# Mosfets.net
KiCad netlist of a schematic drawn in Altium Designer
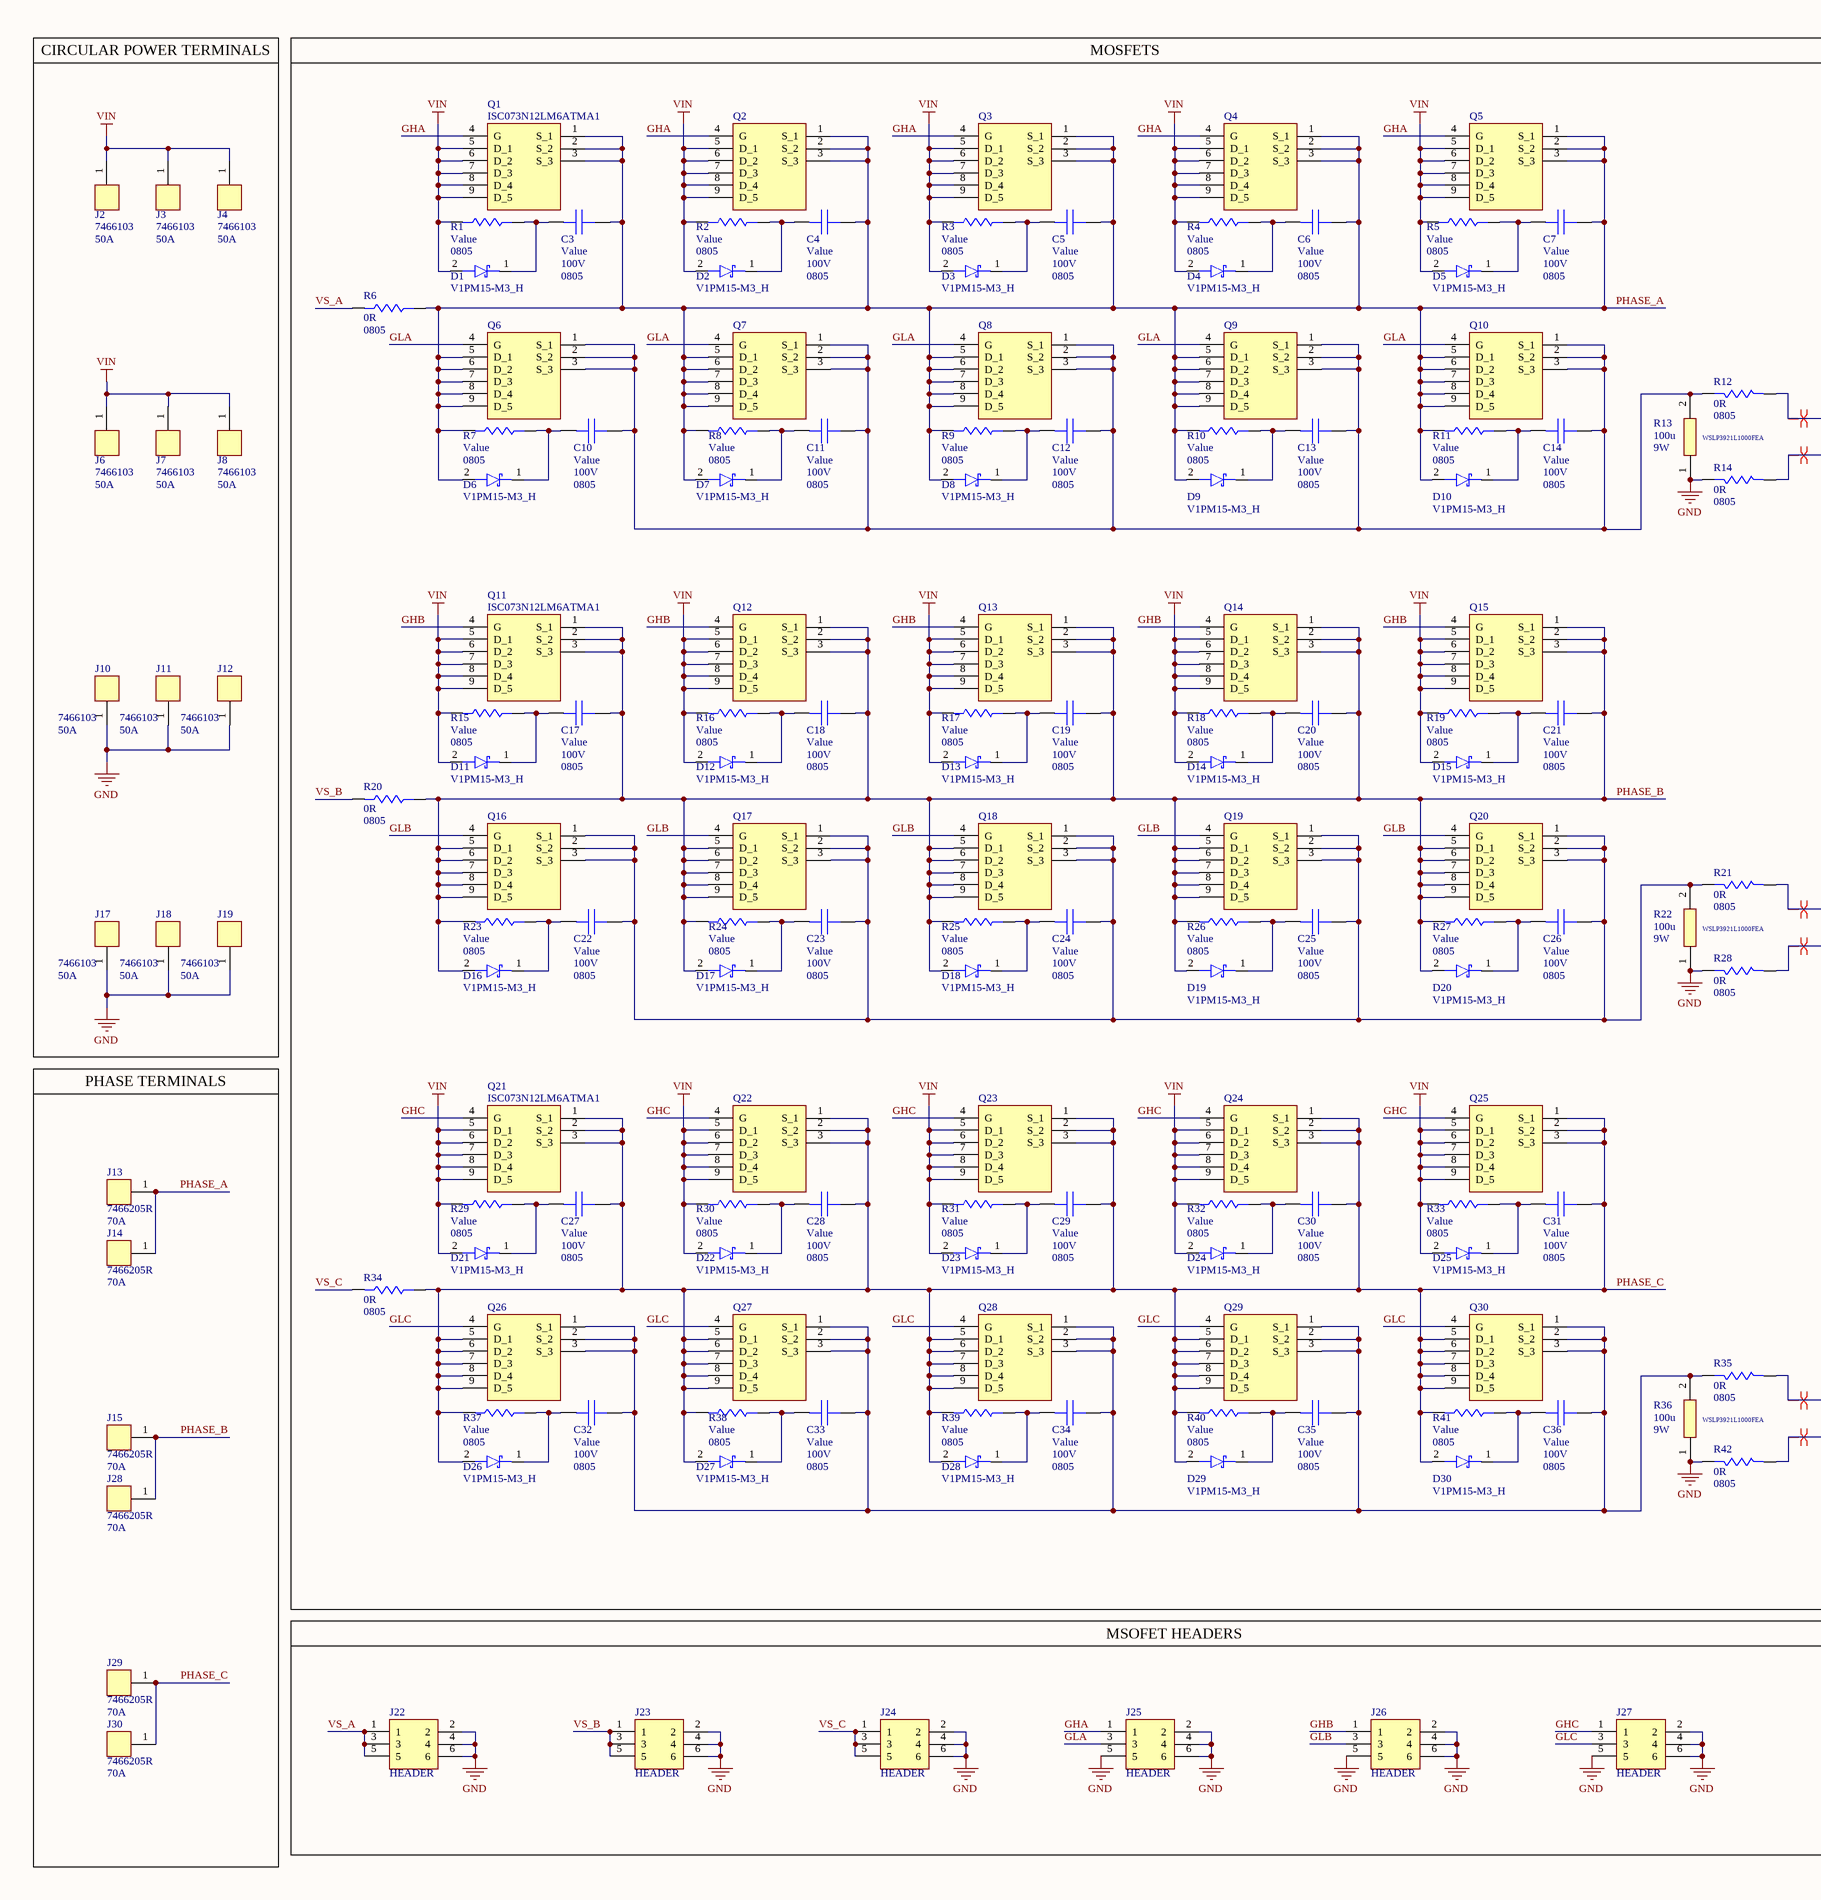
[diagram p0: Mosfets.SchDoc, left]
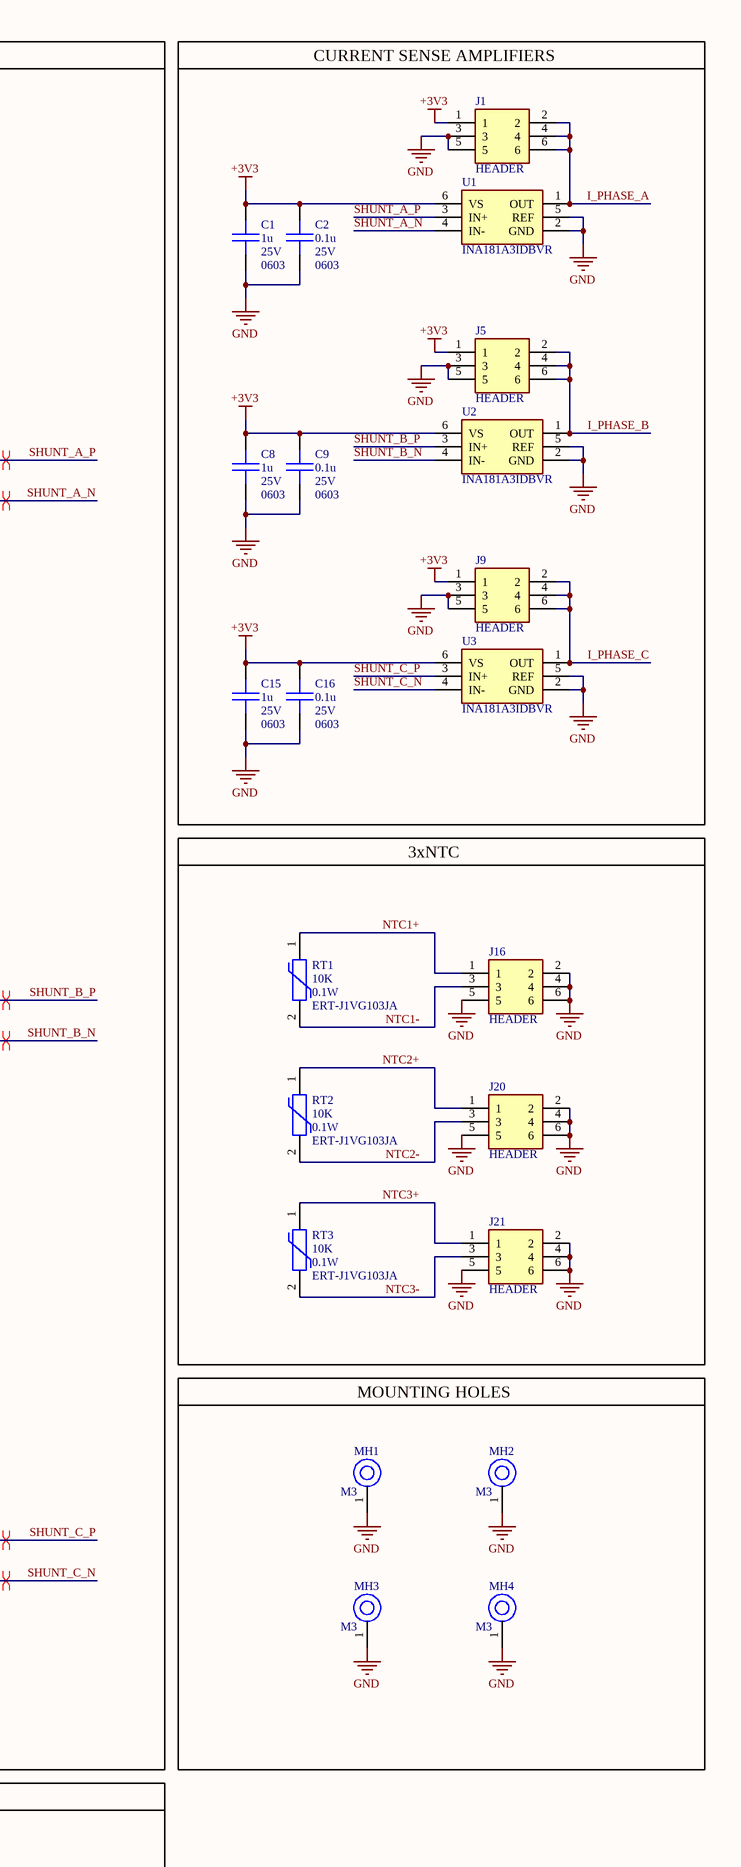
[diagram p1: Mosfets.SchDoc, right]

(export (version "E")
  (design (tool "Eeschema 10.0.6"))
  (components
    (comp (ref "C1")
      (value "0603")
      (footprint "C_0603")
      (description "SMD Chip Capacitor - 0603")
      (fields (field (name "VOLTAGE") "25V") (field (name "ALTIUM_VALUE") "1u"))
      (libsource (lib "My_Integrated_Lib") (part "CAP_0603"))
    )
    (comp (ref "C2")
      (value "0603")
      (footprint "C_0603")
      (description "SMD Chip Capacitor - 0603")
      (fields (field (name "VOLTAGE") "25V") (field (name "ALTIUM_VALUE") "0.1u"))
      (libsource (lib "My_Integrated_Lib") (part "CAP_0603"))
    )
    (comp (ref "C3")
      (value "0805")
      (footprint "C_0805")
      (description "SMD Chip Capacitor - 0805")
      (fields (field (name "VOLTAGE") "100V") (field (name "ALTIUM_VALUE") "Value"))
      (libsource (lib "My_Integrated_Lib") (part "CAP_0805"))
    )
    (comp (ref "C4")
      (value "0805")
      (footprint "C_0805")
      (description "SMD Chip Capacitor - 0805")
      (fields (field (name "VOLTAGE") "100V") (field (name "ALTIUM_VALUE") "Value"))
      (libsource (lib "My_Integrated_Lib") (part "CAP_0805"))
    )
    (comp (ref "C5")
      (value "0805")
      (footprint "C_0805")
      (description "SMD Chip Capacitor - 0805")
      (fields (field (name "VOLTAGE") "100V") (field (name "ALTIUM_VALUE") "Value"))
      (libsource (lib "My_Integrated_Lib") (part "CAP_0805"))
    )
    (comp (ref "C6")
      (value "0805")
      (footprint "C_0805")
      (description "SMD Chip Capacitor - 0805")
      (fields (field (name "VOLTAGE") "100V") (field (name "ALTIUM_VALUE") "Value"))
      (libsource (lib "My_Integrated_Lib") (part "CAP_0805"))
    )
    (comp (ref "C7")
      (value "0805")
      (footprint "C_0805")
      (description "SMD Chip Capacitor - 0805")
      (fields (field (name "VOLTAGE") "100V") (field (name "ALTIUM_VALUE") "Value"))
      (libsource (lib "My_Integrated_Lib") (part "CAP_0805"))
    )
    (comp (ref "C8")
      (value "0603")
      (footprint "C_0603")
      (description "SMD Chip Capacitor - 0603")
      (fields (field (name "VOLTAGE") "25V") (field (name "ALTIUM_VALUE") "1u"))
      (libsource (lib "My_Integrated_Lib") (part "CAP_0603"))
    )
    (comp (ref "C9")
      (value "0603")
      (footprint "C_0603")
      (description "SMD Chip Capacitor - 0603")
      (fields (field (name "VOLTAGE") "25V") (field (name "ALTIUM_VALUE") "0.1u"))
      (libsource (lib "My_Integrated_Lib") (part "CAP_0603"))
    )
    (comp (ref "C10")
      (value "0805")
      (footprint "C_0805")
      (description "SMD Chip Capacitor - 0805")
      (fields (field (name "VOLTAGE") "100V") (field (name "ALTIUM_VALUE") "Value"))
      (libsource (lib "My_Integrated_Lib") (part "CAP_0805"))
    )
    (comp (ref "C11")
      (value "0805")
      (footprint "C_0805")
      (description "SMD Chip Capacitor - 0805")
      (fields (field (name "VOLTAGE") "100V") (field (name "ALTIUM_VALUE") "Value"))
      (libsource (lib "My_Integrated_Lib") (part "CAP_0805"))
    )
    (comp (ref "C12")
      (value "0805")
      (footprint "C_0805")
      (description "SMD Chip Capacitor - 0805")
      (fields (field (name "VOLTAGE") "100V") (field (name "ALTIUM_VALUE") "Value"))
      (libsource (lib "My_Integrated_Lib") (part "CAP_0805"))
    )
    (comp (ref "C13")
      (value "0805")
      (footprint "C_0805")
      (description "SMD Chip Capacitor - 0805")
      (fields (field (name "VOLTAGE") "100V") (field (name "ALTIUM_VALUE") "Value"))
      (libsource (lib "My_Integrated_Lib") (part "CAP_0805"))
    )
    (comp (ref "C14")
      (value "0805")
      (footprint "C_0805")
      (description "SMD Chip Capacitor - 0805")
      (fields (field (name "VOLTAGE") "100V") (field (name "ALTIUM_VALUE") "Value"))
      (libsource (lib "My_Integrated_Lib") (part "CAP_0805"))
    )
    (comp (ref "C15")
      (value "0603")
      (footprint "C_0603")
      (description "SMD Chip Capacitor - 0603")
      (fields (field (name "VOLTAGE") "25V") (field (name "ALTIUM_VALUE") "1u"))
      (libsource (lib "My_Integrated_Lib") (part "CAP_0603"))
    )
    (comp (ref "C16")
      (value "0603")
      (footprint "C_0603")
      (description "SMD Chip Capacitor - 0603")
      (fields (field (name "VOLTAGE") "25V") (field (name "ALTIUM_VALUE") "0.1u"))
      (libsource (lib "My_Integrated_Lib") (part "CAP_0603"))
    )
    (comp (ref "C17")
      (value "0805")
      (footprint "C_0805")
      (description "SMD Chip Capacitor - 0805")
      (fields (field (name "VOLTAGE") "100V") (field (name "ALTIUM_VALUE") "Value"))
      (libsource (lib "My_Integrated_Lib") (part "CAP_0805"))
    )
    (comp (ref "C18")
      (value "0805")
      (footprint "C_0805")
      (description "SMD Chip Capacitor - 0805")
      (fields (field (name "VOLTAGE") "100V") (field (name "ALTIUM_VALUE") "Value"))
      (libsource (lib "My_Integrated_Lib") (part "CAP_0805"))
    )
    (comp (ref "C19")
      (value "0805")
      (footprint "C_0805")
      (description "SMD Chip Capacitor - 0805")
      (fields (field (name "VOLTAGE") "100V") (field (name "ALTIUM_VALUE") "Value"))
      (libsource (lib "My_Integrated_Lib") (part "CAP_0805"))
    )
    (comp (ref "C20")
      (value "0805")
      (footprint "C_0805")
      (description "SMD Chip Capacitor - 0805")
      (fields (field (name "VOLTAGE") "100V") (field (name "ALTIUM_VALUE") "Value"))
      (libsource (lib "My_Integrated_Lib") (part "CAP_0805"))
    )
    (comp (ref "C21")
      (value "0805")
      (footprint "C_0805")
      (description "SMD Chip Capacitor - 0805")
      (fields (field (name "VOLTAGE") "100V") (field (name "ALTIUM_VALUE") "Value"))
      (libsource (lib "My_Integrated_Lib") (part "CAP_0805"))
    )
    (comp (ref "C22")
      (value "0805")
      (footprint "C_0805")
      (description "SMD Chip Capacitor - 0805")
      (fields (field (name "VOLTAGE") "100V") (field (name "ALTIUM_VALUE") "Value"))
      (libsource (lib "My_Integrated_Lib") (part "CAP_0805"))
    )
    (comp (ref "C23")
      (value "0805")
      (footprint "C_0805")
      (description "SMD Chip Capacitor - 0805")
      (fields (field (name "VOLTAGE") "100V") (field (name "ALTIUM_VALUE") "Value"))
      (libsource (lib "My_Integrated_Lib") (part "CAP_0805"))
    )
    (comp (ref "C24")
      (value "0805")
      (footprint "C_0805")
      (description "SMD Chip Capacitor - 0805")
      (fields (field (name "VOLTAGE") "100V") (field (name "ALTIUM_VALUE") "Value"))
      (libsource (lib "My_Integrated_Lib") (part "CAP_0805"))
    )
    (comp (ref "C25")
      (value "0805")
      (footprint "C_0805")
      (description "SMD Chip Capacitor - 0805")
      (fields (field (name "VOLTAGE") "100V") (field (name "ALTIUM_VALUE") "Value"))
      (libsource (lib "My_Integrated_Lib") (part "CAP_0805"))
    )
    (comp (ref "C26")
      (value "0805")
      (footprint "C_0805")
      (description "SMD Chip Capacitor - 0805")
      (fields (field (name "VOLTAGE") "100V") (field (name "ALTIUM_VALUE") "Value"))
      (libsource (lib "My_Integrated_Lib") (part "CAP_0805"))
    )
    (comp (ref "C27")
      (value "0805")
      (footprint "C_0805")
      (description "SMD Chip Capacitor - 0805")
      (fields (field (name "VOLTAGE") "100V") (field (name "ALTIUM_VALUE") "Value"))
      (libsource (lib "My_Integrated_Lib") (part "CAP_0805"))
    )
    (comp (ref "C28")
      (value "0805")
      (footprint "C_0805")
      (description "SMD Chip Capacitor - 0805")
      (fields (field (name "VOLTAGE") "100V") (field (name "ALTIUM_VALUE") "Value"))
      (libsource (lib "My_Integrated_Lib") (part "CAP_0805"))
    )
    (comp (ref "C29")
      (value "0805")
      (footprint "C_0805")
      (description "SMD Chip Capacitor - 0805")
      (fields (field (name "VOLTAGE") "100V") (field (name "ALTIUM_VALUE") "Value"))
      (libsource (lib "My_Integrated_Lib") (part "CAP_0805"))
    )
    (comp (ref "C30")
      (value "0805")
      (footprint "C_0805")
      (description "SMD Chip Capacitor - 0805")
      (fields (field (name "VOLTAGE") "100V") (field (name "ALTIUM_VALUE") "Value"))
      (libsource (lib "My_Integrated_Lib") (part "CAP_0805"))
    )
    (comp (ref "C31")
      (value "0805")
      (footprint "C_0805")
      (description "SMD Chip Capacitor - 0805")
      (fields (field (name "VOLTAGE") "100V") (field (name "ALTIUM_VALUE") "Value"))
      (libsource (lib "My_Integrated_Lib") (part "CAP_0805"))
    )
    (comp (ref "C32")
      (value "0805")
      (footprint "C_0805")
      (description "SMD Chip Capacitor - 0805")
      (fields (field (name "VOLTAGE") "100V") (field (name "ALTIUM_VALUE") "Value"))
      (libsource (lib "My_Integrated_Lib") (part "CAP_0805"))
    )
    (comp (ref "C33")
      (value "0805")
      (footprint "C_0805")
      (description "SMD Chip Capacitor - 0805")
      (fields (field (name "VOLTAGE") "100V") (field (name "ALTIUM_VALUE") "Value"))
      (libsource (lib "My_Integrated_Lib") (part "CAP_0805"))
    )
    (comp (ref "C34")
      (value "0805")
      (footprint "C_0805")
      (description "SMD Chip Capacitor - 0805")
      (fields (field (name "VOLTAGE") "100V") (field (name "ALTIUM_VALUE") "Value"))
      (libsource (lib "My_Integrated_Lib") (part "CAP_0805"))
    )
    (comp (ref "C35")
      (value "0805")
      (footprint "C_0805")
      (description "SMD Chip Capacitor - 0805")
      (fields (field (name "VOLTAGE") "100V") (field (name "ALTIUM_VALUE") "Value"))
      (libsource (lib "My_Integrated_Lib") (part "CAP_0805"))
    )
    (comp (ref "C36")
      (value "0805")
      (footprint "C_0805")
      (description "SMD Chip Capacitor - 0805")
      (fields (field (name "VOLTAGE") "100V") (field (name "ALTIUM_VALUE") "Value"))
      (libsource (lib "My_Integrated_Lib") (part "CAP_0805"))
    )
    (comp (ref "D1")
      (value "V1PM15-M3_H")
      (footprint "DO-219AD-2")
      (description "Schottky Diode, 150V, 1A, Vf: 1.13V")
      (libsource (lib "My_Integrated_Lib") (part "DIODE_SCHOTTKY_V1PM15-M3_H"))
    )
    (comp (ref "D2")
      (value "V1PM15-M3_H")
      (footprint "DO-219AD-2")
      (description "Schottky Diode, 150V, 1A, Vf: 1.13V")
      (libsource (lib "My_Integrated_Lib") (part "DIODE_SCHOTTKY_V1PM15-M3_H"))
    )
    (comp (ref "D3")
      (value "V1PM15-M3_H")
      (footprint "DO-219AD-2")
      (description "Schottky Diode, 150V, 1A, Vf: 1.13V")
      (libsource (lib "My_Integrated_Lib") (part "DIODE_SCHOTTKY_V1PM15-M3_H"))
    )
    (comp (ref "D4")
      (value "V1PM15-M3_H")
      (footprint "DO-219AD-2")
      (description "Schottky Diode, 150V, 1A, Vf: 1.13V")
      (libsource (lib "My_Integrated_Lib") (part "DIODE_SCHOTTKY_V1PM15-M3_H"))
    )
    (comp (ref "D5")
      (value "V1PM15-M3_H")
      (footprint "DO-219AD-2")
      (description "Schottky Diode, 150V, 1A, Vf: 1.13V")
      (libsource (lib "My_Integrated_Lib") (part "DIODE_SCHOTTKY_V1PM15-M3_H"))
    )
    (comp (ref "D6")
      (value "V1PM15-M3_H")
      (footprint "DO-219AD-2")
      (description "Schottky Diode, 150V, 1A, Vf: 1.13V")
      (libsource (lib "My_Integrated_Lib") (part "DIODE_SCHOTTKY_V1PM15-M3_H"))
    )
    (comp (ref "D7")
      (value "V1PM15-M3_H")
      (footprint "DO-219AD-2")
      (description "Schottky Diode, 150V, 1A, Vf: 1.13V")
      (libsource (lib "My_Integrated_Lib") (part "DIODE_SCHOTTKY_V1PM15-M3_H"))
    )
    (comp (ref "D8")
      (value "V1PM15-M3_H")
      (footprint "DO-219AD-2")
      (description "Schottky Diode, 150V, 1A, Vf: 1.13V")
      (libsource (lib "My_Integrated_Lib") (part "DIODE_SCHOTTKY_V1PM15-M3_H"))
    )
    (comp (ref "D9")
      (value "V1PM15-M3_H")
      (footprint "DO-219AD-2")
      (description "Schottky Diode, 150V, 1A, Vf: 1.13V")
      (libsource (lib "My_Integrated_Lib") (part "DIODE_SCHOTTKY_V1PM15-M3_H"))
    )
    (comp (ref "D10")
      (value "V1PM15-M3_H")
      (footprint "DO-219AD-2")
      (description "Schottky Diode, 150V, 1A, Vf: 1.13V")
      (libsource (lib "My_Integrated_Lib") (part "DIODE_SCHOTTKY_V1PM15-M3_H"))
    )
    (comp (ref "D11")
      (value "V1PM15-M3_H")
      (footprint "DO-219AD-2")
      (description "Schottky Diode, 150V, 1A, Vf: 1.13V")
      (libsource (lib "My_Integrated_Lib") (part "DIODE_SCHOTTKY_V1PM15-M3_H"))
    )
    (comp (ref "D12")
      (value "V1PM15-M3_H")
      (footprint "DO-219AD-2")
      (description "Schottky Diode, 150V, 1A, Vf: 1.13V")
      (libsource (lib "My_Integrated_Lib") (part "DIODE_SCHOTTKY_V1PM15-M3_H"))
    )
    (comp (ref "D13")
      (value "V1PM15-M3_H")
      (footprint "DO-219AD-2")
      (description "Schottky Diode, 150V, 1A, Vf: 1.13V")
      (libsource (lib "My_Integrated_Lib") (part "DIODE_SCHOTTKY_V1PM15-M3_H"))
    )
    (comp (ref "D14")
      (value "V1PM15-M3_H")
      (footprint "DO-219AD-2")
      (description "Schottky Diode, 150V, 1A, Vf: 1.13V")
      (libsource (lib "My_Integrated_Lib") (part "DIODE_SCHOTTKY_V1PM15-M3_H"))
    )
    (comp (ref "D15")
      (value "V1PM15-M3_H")
      (footprint "DO-219AD-2")
      (description "Schottky Diode, 150V, 1A, Vf: 1.13V")
      (libsource (lib "My_Integrated_Lib") (part "DIODE_SCHOTTKY_V1PM15-M3_H"))
    )
    (comp (ref "D16")
      (value "V1PM15-M3_H")
      (footprint "DO-219AD-2")
      (description "Schottky Diode, 150V, 1A, Vf: 1.13V")
      (libsource (lib "My_Integrated_Lib") (part "DIODE_SCHOTTKY_V1PM15-M3_H"))
    )
    (comp (ref "D17")
      (value "V1PM15-M3_H")
      (footprint "DO-219AD-2")
      (description "Schottky Diode, 150V, 1A, Vf: 1.13V")
      (libsource (lib "My_Integrated_Lib") (part "DIODE_SCHOTTKY_V1PM15-M3_H"))
    )
    (comp (ref "D18")
      (value "V1PM15-M3_H")
      (footprint "DO-219AD-2")
      (description "Schottky Diode, 150V, 1A, Vf: 1.13V")
      (libsource (lib "My_Integrated_Lib") (part "DIODE_SCHOTTKY_V1PM15-M3_H"))
    )
    (comp (ref "D19")
      (value "V1PM15-M3_H")
      (footprint "DO-219AD-2")
      (description "Schottky Diode, 150V, 1A, Vf: 1.13V")
      (libsource (lib "My_Integrated_Lib") (part "DIODE_SCHOTTKY_V1PM15-M3_H"))
    )
    (comp (ref "D20")
      (value "V1PM15-M3_H")
      (footprint "DO-219AD-2")
      (description "Schottky Diode, 150V, 1A, Vf: 1.13V")
      (libsource (lib "My_Integrated_Lib") (part "DIODE_SCHOTTKY_V1PM15-M3_H"))
    )
    (comp (ref "D21")
      (value "V1PM15-M3_H")
      (footprint "DO-219AD-2")
      (description "Schottky Diode, 150V, 1A, Vf: 1.13V")
      (libsource (lib "My_Integrated_Lib") (part "DIODE_SCHOTTKY_V1PM15-M3_H"))
    )
    (comp (ref "D22")
      (value "V1PM15-M3_H")
      (footprint "DO-219AD-2")
      (description "Schottky Diode, 150V, 1A, Vf: 1.13V")
      (libsource (lib "My_Integrated_Lib") (part "DIODE_SCHOTTKY_V1PM15-M3_H"))
    )
    (comp (ref "D23")
      (value "V1PM15-M3_H")
      (footprint "DO-219AD-2")
      (description "Schottky Diode, 150V, 1A, Vf: 1.13V")
      (libsource (lib "My_Integrated_Lib") (part "DIODE_SCHOTTKY_V1PM15-M3_H"))
    )
    (comp (ref "D24")
      (value "V1PM15-M3_H")
      (footprint "DO-219AD-2")
      (description "Schottky Diode, 150V, 1A, Vf: 1.13V")
      (libsource (lib "My_Integrated_Lib") (part "DIODE_SCHOTTKY_V1PM15-M3_H"))
    )
    (comp (ref "D25")
      (value "V1PM15-M3_H")
      (footprint "DO-219AD-2")
      (description "Schottky Diode, 150V, 1A, Vf: 1.13V")
      (libsource (lib "My_Integrated_Lib") (part "DIODE_SCHOTTKY_V1PM15-M3_H"))
    )
    (comp (ref "D26")
      (value "V1PM15-M3_H")
      (footprint "DO-219AD-2")
      (description "Schottky Diode, 150V, 1A, Vf: 1.13V")
      (libsource (lib "My_Integrated_Lib") (part "DIODE_SCHOTTKY_V1PM15-M3_H"))
    )
    (comp (ref "D27")
      (value "V1PM15-M3_H")
      (footprint "DO-219AD-2")
      (description "Schottky Diode, 150V, 1A, Vf: 1.13V")
      (libsource (lib "My_Integrated_Lib") (part "DIODE_SCHOTTKY_V1PM15-M3_H"))
    )
    (comp (ref "D28")
      (value "V1PM15-M3_H")
      (footprint "DO-219AD-2")
      (description "Schottky Diode, 150V, 1A, Vf: 1.13V")
      (libsource (lib "My_Integrated_Lib") (part "DIODE_SCHOTTKY_V1PM15-M3_H"))
    )
    (comp (ref "D29")
      (value "V1PM15-M3_H")
      (footprint "DO-219AD-2")
      (description "Schottky Diode, 150V, 1A, Vf: 1.13V")
      (libsource (lib "My_Integrated_Lib") (part "DIODE_SCHOTTKY_V1PM15-M3_H"))
    )
    (comp (ref "D30")
      (value "V1PM15-M3_H")
      (footprint "DO-219AD-2")
      (description "Schottky Diode, 150V, 1A, Vf: 1.13V")
      (libsource (lib "My_Integrated_Lib") (part "DIODE_SCHOTTKY_V1PM15-M3_H"))
    )
    (comp (ref "J1")
      (value "HEADER")
      (footprint "HEADER_MALE_2X3_1.27MM")
      (libsource (lib "My_Integrated_Lib") (part "HEADER_SMD_2X3_1.27MM"))
    )
    (comp (ref "J2")
      (value "7466103")
      (footprint "7466203")
      (description "Terminals, SMT, M3 Thread, 50A")
      (fields (field (name "CURRENT") "50A"))
      (libsource (lib "My_Integrated_Lib") (part "TERMINAL_7466203"))
    )
    (comp (ref "J3")
      (value "7466103")
      (footprint "7466203")
      (description "Terminals, SMT, M3 Thread, 50A")
      (fields (field (name "CURRENT") "50A"))
      (libsource (lib "My_Integrated_Lib") (part "TERMINAL_7466203"))
    )
    (comp (ref "J4")
      (value "7466103")
      (footprint "7466203")
      (description "Terminals, SMT, M3 Thread, 50A")
      (fields (field (name "CURRENT") "50A"))
      (libsource (lib "My_Integrated_Lib") (part "TERMINAL_7466203"))
    )
    (comp (ref "J5")
      (value "HEADER")
      (footprint "HEADER_MALE_2X3_1.27MM")
      (libsource (lib "My_Integrated_Lib") (part "HEADER_SMD_2X3_1.27MM"))
    )
    (comp (ref "J6")
      (value "7466103")
      (footprint "7466203")
      (description "Terminals, SMT, M3 Thread, 50A")
      (fields (field (name "CURRENT") "50A"))
      (libsource (lib "My_Integrated_Lib") (part "TERMINAL_7466203"))
    )
    (comp (ref "J7")
      (value "7466103")
      (footprint "7466203")
      (description "Terminals, SMT, M3 Thread, 50A")
      (fields (field (name "CURRENT") "50A"))
      (libsource (lib "My_Integrated_Lib") (part "TERMINAL_7466203"))
    )
    (comp (ref "J8")
      (value "7466103")
      (footprint "7466203")
      (description "Terminals, SMT, M3 Thread, 50A")
      (fields (field (name "CURRENT") "50A"))
      (libsource (lib "My_Integrated_Lib") (part "TERMINAL_7466203"))
    )
    (comp (ref "J9")
      (value "HEADER")
      (footprint "HEADER_MALE_2X3_1.27MM")
      (libsource (lib "My_Integrated_Lib") (part "HEADER_SMD_2X3_1.27MM"))
    )
    (comp (ref "J10")
      (value "7466103")
      (footprint "7466203")
      (description "Terminals, SMT, M3 Thread, 50A")
      (fields (field (name "CURRENT") "50A"))
      (libsource (lib "") (part "TERMINAL_7466203_1"))
    )
    (comp (ref "J11")
      (value "7466103")
      (footprint "7466203")
      (description "Terminals, SMT, M3 Thread, 50A")
      (fields (field (name "CURRENT") "50A"))
      (libsource (lib "") (part "TERMINAL_7466203_1"))
    )
    (comp (ref "J12")
      (value "7466103")
      (footprint "7466203")
      (description "Terminals, SMT, M3 Thread, 50A")
      (fields (field (name "CURRENT") "50A"))
      (libsource (lib "") (part "TERMINAL_7466203_1"))
    )
    (comp (ref "J13")
      (value "7466205R")
      (footprint "7466205R")
      (description "Terminals, SMT, M5 Thread, 70A")
      (fields (field (name "CURRENT") "70A"))
      (libsource (lib "My_Integrated_Lib") (part "TERMINAL_7466205R"))
    )
    (comp (ref "J14")
      (value "7466205R")
      (footprint "7466205R")
      (description "Terminals, SMT, M5 Thread, 70A")
      (fields (field (name "CURRENT") "70A"))
      (libsource (lib "My_Integrated_Lib") (part "TERMINAL_7466205R"))
    )
    (comp (ref "J15")
      (value "7466205R")
      (footprint "7466205R")
      (description "Terminals, SMT, M5 Thread, 70A")
      (fields (field (name "CURRENT") "70A"))
      (libsource (lib "My_Integrated_Lib") (part "TERMINAL_7466205R"))
    )
    (comp (ref "J16")
      (value "HEADER")
      (footprint "HEADER_MALE_2X3_1.27MM")
      (libsource (lib "My_Integrated_Lib") (part "HEADER_SMD_2X3_1.27MM"))
    )
    (comp (ref "J17")
      (value "7466103")
      (footprint "7466203")
      (description "Terminals, SMT, M3 Thread, 50A")
      (fields (field (name "CURRENT") "50A"))
      (libsource (lib "") (part "TERMINAL_7466203_1"))
    )
    (comp (ref "J18")
      (value "7466103")
      (footprint "7466203")
      (description "Terminals, SMT, M3 Thread, 50A")
      (fields (field (name "CURRENT") "50A"))
      (libsource (lib "") (part "TERMINAL_7466203_1"))
    )
    (comp (ref "J19")
      (value "7466103")
      (footprint "7466203")
      (description "Terminals, SMT, M3 Thread, 50A")
      (fields (field (name "CURRENT") "50A"))
      (libsource (lib "") (part "TERMINAL_7466203_1"))
    )
    (comp (ref "J20")
      (value "HEADER")
      (footprint "HEADER_MALE_2X3_1.27MM")
      (libsource (lib "My_Integrated_Lib") (part "HEADER_SMD_2X3_1.27MM"))
    )
    (comp (ref "J21")
      (value "HEADER")
      (footprint "HEADER_MALE_2X3_1.27MM")
      (libsource (lib "My_Integrated_Lib") (part "HEADER_SMD_2X3_1.27MM"))
    )
    (comp (ref "J22")
      (value "HEADER")
      (footprint "HEADER_MALE_2X3_1.27MM")
      (libsource (lib "My_Integrated_Lib") (part "HEADER_SMD_2X3_1.27MM"))
    )
    (comp (ref "J23")
      (value "HEADER")
      (footprint "HEADER_MALE_2X3_1.27MM")
      (libsource (lib "My_Integrated_Lib") (part "HEADER_SMD_2X3_1.27MM"))
    )
    (comp (ref "J24")
      (value "HEADER")
      (footprint "HEADER_MALE_2X3_1.27MM")
      (libsource (lib "My_Integrated_Lib") (part "HEADER_SMD_2X3_1.27MM"))
    )
    (comp (ref "J25")
      (value "HEADER")
      (footprint "HEADER_MALE_2X3_1.27MM")
      (libsource (lib "My_Integrated_Lib") (part "HEADER_SMD_2X3_1.27MM"))
    )
    (comp (ref "J26")
      (value "HEADER")
      (footprint "HEADER_MALE_2X3_1.27MM")
      (libsource (lib "My_Integrated_Lib") (part "HEADER_SMD_2X3_1.27MM"))
    )
    (comp (ref "J27")
      (value "HEADER")
      (footprint "HEADER_MALE_2X3_1.27MM")
      (libsource (lib "My_Integrated_Lib") (part "HEADER_SMD_2X3_1.27MM"))
    )
    (comp (ref "J28")
      (value "7466205R")
      (footprint "7466205R")
      (description "Terminals, SMT, M5 Thread, 70A")
      (fields (field (name "CURRENT") "70A"))
      (libsource (lib "My_Integrated_Lib") (part "TERMINAL_7466205R"))
    )
    (comp (ref "J29")
      (value "7466205R")
      (footprint "7466205R")
      (description "Terminals, SMT, M5 Thread, 70A")
      (fields (field (name "CURRENT") "70A"))
      (libsource (lib "My_Integrated_Lib") (part "TERMINAL_7466205R"))
    )
    (comp (ref "J30")
      (value "7466205R")
      (footprint "7466205R")
      (description "Terminals, SMT, M5 Thread, 70A")
      (fields (field (name "CURRENT") "70A"))
      (libsource (lib "My_Integrated_Lib") (part "TERMINAL_7466205R"))
    )
    (comp (ref "MH1")
      (value "M3")
      (footprint "MOUNTING_HOLE_M3")
      (description "M3 Mounting Hole")
      (libsource (lib "My_Integrated_Lib") (part "Mounting_Hole_M3"))
    )
    (comp (ref "MH2")
      (value "M3")
      (footprint "MOUNTING_HOLE_M3")
      (description "M3 Mounting Hole")
      (libsource (lib "My_Integrated_Lib") (part "Mounting_Hole_M3"))
    )
    (comp (ref "MH3")
      (value "M3")
      (footprint "MOUNTING_HOLE_M3")
      (description "M3 Mounting Hole")
      (libsource (lib "My_Integrated_Lib") (part "Mounting_Hole_M3"))
    )
    (comp (ref "MH4")
      (value "M3")
      (footprint "MOUNTING_HOLE_M3")
      (description "M3 Mounting Hole")
      (libsource (lib "My_Integrated_Lib") (part "Mounting_Hole_M3"))
    )
    (comp (ref "Q1")
      (value "ISC073N12LM6ATMA1")
      (footprint "TDSON-8")
      (description "N Channel MOSFET, 120V, 86A, 7.3mR")
      (libsource (lib "My_Integrated_Lib") (part "MOSFET_N_ISC073N12LM6ATMA1"))
    )
    (comp (ref "Q2")
      (value "ISC073N12LM6ATMA1")
      (footprint "TDSON-8")
      (description "N Channel MOSFET, 120V, 86A, 7.3mR")
      (libsource (lib "My_Integrated_Lib") (part "MOSFET_N_ISC073N12LM6ATMA1"))
    )
    (comp (ref "Q3")
      (value "ISC073N12LM6ATMA1")
      (footprint "TDSON-8")
      (description "N Channel MOSFET, 120V, 86A, 7.3mR")
      (libsource (lib "My_Integrated_Lib") (part "MOSFET_N_ISC073N12LM6ATMA1"))
    )
    (comp (ref "Q4")
      (value "ISC073N12LM6ATMA1")
      (footprint "TDSON-8")
      (description "N Channel MOSFET, 120V, 86A, 7.3mR")
      (libsource (lib "My_Integrated_Lib") (part "MOSFET_N_ISC073N12LM6ATMA1"))
    )
    (comp (ref "Q5")
      (value "ISC073N12LM6ATMA1")
      (footprint "TDSON-8")
      (description "N Channel MOSFET, 120V, 86A, 7.3mR")
      (libsource (lib "My_Integrated_Lib") (part "MOSFET_N_ISC073N12LM6ATMA1"))
    )
    (comp (ref "Q6")
      (value "ISC073N12LM6ATMA1")
      (footprint "TDSON-8")
      (description "N Channel MOSFET, 120V, 86A, 7.3mR")
      (libsource (lib "My_Integrated_Lib") (part "MOSFET_N_ISC073N12LM6ATMA1"))
    )
    (comp (ref "Q7")
      (value "ISC073N12LM6ATMA1")
      (footprint "TDSON-8")
      (description "N Channel MOSFET, 120V, 86A, 7.3mR")
      (libsource (lib "My_Integrated_Lib") (part "MOSFET_N_ISC073N12LM6ATMA1"))
    )
    (comp (ref "Q8")
      (value "ISC073N12LM6ATMA1")
      (footprint "TDSON-8")
      (description "N Channel MOSFET, 120V, 86A, 7.3mR")
      (libsource (lib "My_Integrated_Lib") (part "MOSFET_N_ISC073N12LM6ATMA1"))
    )
    (comp (ref "Q9")
      (value "ISC073N12LM6ATMA1")
      (footprint "TDSON-8")
      (description "N Channel MOSFET, 120V, 86A, 7.3mR")
      (libsource (lib "My_Integrated_Lib") (part "MOSFET_N_ISC073N12LM6ATMA1"))
    )
    (comp (ref "Q10")
      (value "ISC073N12LM6ATMA1")
      (footprint "TDSON-8")
      (description "N Channel MOSFET, 120V, 86A, 7.3mR")
      (libsource (lib "My_Integrated_Lib") (part "MOSFET_N_ISC073N12LM6ATMA1"))
    )
    (comp (ref "Q11")
      (value "ISC073N12LM6ATMA1")
      (footprint "TDSON-8")
      (description "N Channel MOSFET, 120V, 86A, 7.3mR")
      (libsource (lib "My_Integrated_Lib") (part "MOSFET_N_ISC073N12LM6ATMA1"))
    )
    (comp (ref "Q12")
      (value "ISC073N12LM6ATMA1")
      (footprint "TDSON-8")
      (description "N Channel MOSFET, 120V, 86A, 7.3mR")
      (libsource (lib "My_Integrated_Lib") (part "MOSFET_N_ISC073N12LM6ATMA1"))
    )
    (comp (ref "Q13")
      (value "ISC073N12LM6ATMA1")
      (footprint "TDSON-8")
      (description "N Channel MOSFET, 120V, 86A, 7.3mR")
      (libsource (lib "My_Integrated_Lib") (part "MOSFET_N_ISC073N12LM6ATMA1"))
    )
    (comp (ref "Q14")
      (value "ISC073N12LM6ATMA1")
      (footprint "TDSON-8")
      (description "N Channel MOSFET, 120V, 86A, 7.3mR")
      (libsource (lib "My_Integrated_Lib") (part "MOSFET_N_ISC073N12LM6ATMA1"))
    )
    (comp (ref "Q15")
      (value "ISC073N12LM6ATMA1")
      (footprint "TDSON-8")
      (description "N Channel MOSFET, 120V, 86A, 7.3mR")
      (libsource (lib "My_Integrated_Lib") (part "MOSFET_N_ISC073N12LM6ATMA1"))
    )
    (comp (ref "Q16")
      (value "ISC073N12LM6ATMA1")
      (footprint "TDSON-8")
      (description "N Channel MOSFET, 120V, 86A, 7.3mR")
      (libsource (lib "My_Integrated_Lib") (part "MOSFET_N_ISC073N12LM6ATMA1"))
    )
    (comp (ref "Q17")
      (value "ISC073N12LM6ATMA1")
      (footprint "TDSON-8")
      (description "N Channel MOSFET, 120V, 86A, 7.3mR")
      (libsource (lib "My_Integrated_Lib") (part "MOSFET_N_ISC073N12LM6ATMA1"))
    )
    (comp (ref "Q18")
      (value "ISC073N12LM6ATMA1")
      (footprint "TDSON-8")
      (description "N Channel MOSFET, 120V, 86A, 7.3mR")
      (libsource (lib "My_Integrated_Lib") (part "MOSFET_N_ISC073N12LM6ATMA1"))
    )
    (comp (ref "Q19")
      (value "ISC073N12LM6ATMA1")
      (footprint "TDSON-8")
      (description "N Channel MOSFET, 120V, 86A, 7.3mR")
      (libsource (lib "My_Integrated_Lib") (part "MOSFET_N_ISC073N12LM6ATMA1"))
    )
    (comp (ref "Q20")
      (value "ISC073N12LM6ATMA1")
      (footprint "TDSON-8")
      (description "N Channel MOSFET, 120V, 86A, 7.3mR")
      (libsource (lib "My_Integrated_Lib") (part "MOSFET_N_ISC073N12LM6ATMA1"))
    )
    (comp (ref "Q21")
      (value "ISC073N12LM6ATMA1")
      (footprint "TDSON-8")
      (description "N Channel MOSFET, 120V, 86A, 7.3mR")
      (libsource (lib "My_Integrated_Lib") (part "MOSFET_N_ISC073N12LM6ATMA1"))
    )
    (comp (ref "Q22")
      (value "ISC073N12LM6ATMA1")
      (footprint "TDSON-8")
      (description "N Channel MOSFET, 120V, 86A, 7.3mR")
      (libsource (lib "My_Integrated_Lib") (part "MOSFET_N_ISC073N12LM6ATMA1"))
    )
    (comp (ref "Q23")
      (value "ISC073N12LM6ATMA1")
      (footprint "TDSON-8")
      (description "N Channel MOSFET, 120V, 86A, 7.3mR")
      (libsource (lib "My_Integrated_Lib") (part "MOSFET_N_ISC073N12LM6ATMA1"))
    )
    (comp (ref "Q24")
      (value "ISC073N12LM6ATMA1")
      (footprint "TDSON-8")
      (description "N Channel MOSFET, 120V, 86A, 7.3mR")
      (libsource (lib "My_Integrated_Lib") (part "MOSFET_N_ISC073N12LM6ATMA1"))
    )
    (comp (ref "Q25")
      (value "ISC073N12LM6ATMA1")
      (footprint "TDSON-8")
      (description "N Channel MOSFET, 120V, 86A, 7.3mR")
      (libsource (lib "My_Integrated_Lib") (part "MOSFET_N_ISC073N12LM6ATMA1"))
    )
    (comp (ref "Q26")
      (value "ISC073N12LM6ATMA1")
      (footprint "TDSON-8")
      (description "N Channel MOSFET, 120V, 86A, 7.3mR")
      (libsource (lib "My_Integrated_Lib") (part "MOSFET_N_ISC073N12LM6ATMA1"))
    )
    (comp (ref "Q27")
      (value "ISC073N12LM6ATMA1")
      (footprint "TDSON-8")
      (description "N Channel MOSFET, 120V, 86A, 7.3mR")
      (libsource (lib "My_Integrated_Lib") (part "MOSFET_N_ISC073N12LM6ATMA1"))
    )
    (comp (ref "Q28")
      (value "ISC073N12LM6ATMA1")
      (footprint "TDSON-8")
      (description "N Channel MOSFET, 120V, 86A, 7.3mR")
      (libsource (lib "My_Integrated_Lib") (part "MOSFET_N_ISC073N12LM6ATMA1"))
    )
    (comp (ref "Q29")
      (value "ISC073N12LM6ATMA1")
      (footprint "TDSON-8")
      (description "N Channel MOSFET, 120V, 86A, 7.3mR")
      (libsource (lib "My_Integrated_Lib") (part "MOSFET_N_ISC073N12LM6ATMA1"))
    )
    (comp (ref "Q30")
      (value "ISC073N12LM6ATMA1")
      (footprint "TDSON-8")
      (description "N Channel MOSFET, 120V, 86A, 7.3mR")
      (libsource (lib "My_Integrated_Lib") (part "MOSFET_N_ISC073N12LM6ATMA1"))
    )
    (comp (ref "R1")
      (value "0805")
      (footprint "R_0805")
      (description "SMD Chip Resistor - 0805")
      (fields (field (name "TOLERANCE") "?") (field (name "ALTIUM_VALUE") "Value"))
      (libsource (lib "My_Integrated_Lib") (part "RES_0805"))
    )
    (comp (ref "R2")
      (value "0805")
      (footprint "R_0805")
      (description "SMD Chip Resistor - 0805")
      (fields (field (name "TOLERANCE") "?") (field (name "ALTIUM_VALUE") "Value"))
      (libsource (lib "My_Integrated_Lib") (part "RES_0805"))
    )
    (comp (ref "R3")
      (value "0805")
      (footprint "R_0805")
      (description "SMD Chip Resistor - 0805")
      (fields (field (name "TOLERANCE") "?") (field (name "ALTIUM_VALUE") "Value"))
      (libsource (lib "My_Integrated_Lib") (part "RES_0805"))
    )
    (comp (ref "R4")
      (value "0805")
      (footprint "R_0805")
      (description "SMD Chip Resistor - 0805")
      (fields (field (name "TOLERANCE") "?") (field (name "ALTIUM_VALUE") "Value"))
      (libsource (lib "My_Integrated_Lib") (part "RES_0805"))
    )
    (comp (ref "R5")
      (value "0805")
      (footprint "R_0805")
      (description "SMD Chip Resistor - 0805")
      (fields (field (name "TOLERANCE") "?") (field (name "ALTIUM_VALUE") "Value"))
      (libsource (lib "My_Integrated_Lib") (part "RES_0805"))
    )
    (comp (ref "R6")
      (value "0805")
      (footprint "R_0805")
      (description "SMD Chip Resistor - 0805")
      (fields (field (name "TOLERANCE") "?") (field (name "ALTIUM_VALUE") "0R"))
      (libsource (lib "My_Integrated_Lib") (part "RES_0805"))
    )
    (comp (ref "R7")
      (value "0805")
      (footprint "R_0805")
      (description "SMD Chip Resistor - 0805")
      (fields (field (name "TOLERANCE") "?") (field (name "ALTIUM_VALUE") "Value"))
      (libsource (lib "My_Integrated_Lib") (part "RES_0805"))
    )
    (comp (ref "R8")
      (value "0805")
      (footprint "R_0805")
      (description "SMD Chip Resistor - 0805")
      (fields (field (name "TOLERANCE") "?") (field (name "ALTIUM_VALUE") "Value"))
      (libsource (lib "My_Integrated_Lib") (part "RES_0805"))
    )
    (comp (ref "R9")
      (value "0805")
      (footprint "R_0805")
      (description "SMD Chip Resistor - 0805")
      (fields (field (name "TOLERANCE") "?") (field (name "ALTIUM_VALUE") "Value"))
      (libsource (lib "My_Integrated_Lib") (part "RES_0805"))
    )
    (comp (ref "R10")
      (value "0805")
      (footprint "R_0805")
      (description "SMD Chip Resistor - 0805")
      (fields (field (name "TOLERANCE") "?") (field (name "ALTIUM_VALUE") "Value"))
      (libsource (lib "My_Integrated_Lib") (part "RES_0805"))
    )
    (comp (ref "R11")
      (value "0805")
      (footprint "R_0805")
      (description "SMD Chip Resistor - 0805")
      (fields (field (name "TOLERANCE") "?") (field (name "ALTIUM_VALUE") "Value"))
      (libsource (lib "My_Integrated_Lib") (part "RES_0805"))
    )
    (comp (ref "R12")
      (value "0805")
      (footprint "R_0805")
      (description "SMD Chip Resistor - 0805")
      (fields (field (name "TOLERANCE") "?") (field (name "ALTIUM_VALUE") "0R"))
      (libsource (lib "My_Integrated_Lib") (part "RES_0805"))
    )
    (comp (ref "R13")
      (value "WSLP3921L1000FEA")
      (footprint "R_3921")
      (description "Shunt Resistor, 100uR, 9W")
      (fields (field (name "TOLERANCE") "%1") (field (name "ALTIUM_VALUE") "100u") (field (name "WATT") "9W"))
      (libsource (lib "My_Integrated_Lib") (part "RES_SHUNT_100uR_9W"))
    )
    (comp (ref "R14")
      (value "0805")
      (footprint "R_0805")
      (description "SMD Chip Resistor - 0805")
      (fields (field (name "TOLERANCE") "?") (field (name "ALTIUM_VALUE") "0R"))
      (libsource (lib "My_Integrated_Lib") (part "RES_0805"))
    )
    (comp (ref "R15")
      (value "0805")
      (footprint "R_0805")
      (description "SMD Chip Resistor - 0805")
      (fields (field (name "TOLERANCE") "?") (field (name "ALTIUM_VALUE") "Value"))
      (libsource (lib "My_Integrated_Lib") (part "RES_0805"))
    )
    (comp (ref "R16")
      (value "0805")
      (footprint "R_0805")
      (description "SMD Chip Resistor - 0805")
      (fields (field (name "TOLERANCE") "?") (field (name "ALTIUM_VALUE") "Value"))
      (libsource (lib "My_Integrated_Lib") (part "RES_0805"))
    )
    (comp (ref "R17")
      (value "0805")
      (footprint "R_0805")
      (description "SMD Chip Resistor - 0805")
      (fields (field (name "TOLERANCE") "?") (field (name "ALTIUM_VALUE") "Value"))
      (libsource (lib "My_Integrated_Lib") (part "RES_0805"))
    )
    (comp (ref "R18")
      (value "0805")
      (footprint "R_0805")
      (description "SMD Chip Resistor - 0805")
      (fields (field (name "TOLERANCE") "?") (field (name "ALTIUM_VALUE") "Value"))
      (libsource (lib "My_Integrated_Lib") (part "RES_0805"))
    )
    (comp (ref "R19")
      (value "0805")
      (footprint "R_0805")
      (description "SMD Chip Resistor - 0805")
      (fields (field (name "TOLERANCE") "?") (field (name "ALTIUM_VALUE") "Value"))
      (libsource (lib "My_Integrated_Lib") (part "RES_0805"))
    )
    (comp (ref "R20")
      (value "0805")
      (footprint "R_0805")
      (description "SMD Chip Resistor - 0805")
      (fields (field (name "TOLERANCE") "?") (field (name "ALTIUM_VALUE") "0R"))
      (libsource (lib "My_Integrated_Lib") (part "RES_0805"))
    )
    (comp (ref "R21")
      (value "0805")
      (footprint "R_0805")
      (description "SMD Chip Resistor - 0805")
      (fields (field (name "TOLERANCE") "?") (field (name "ALTIUM_VALUE") "0R"))
      (libsource (lib "My_Integrated_Lib") (part "RES_0805"))
    )
    (comp (ref "R22")
      (value "WSLP3921L1000FEA")
      (footprint "R_3921")
      (description "Shunt Resistor, 100uR, 9W")
      (fields (field (name "TOLERANCE") "%1") (field (name "ALTIUM_VALUE") "100u") (field (name "WATT") "9W"))
      (libsource (lib "My_Integrated_Lib") (part "RES_SHUNT_100uR_9W"))
    )
    (comp (ref "R23")
      (value "0805")
      (footprint "R_0805")
      (description "SMD Chip Resistor - 0805")
      (fields (field (name "TOLERANCE") "?") (field (name "ALTIUM_VALUE") "Value"))
      (libsource (lib "My_Integrated_Lib") (part "RES_0805"))
    )
    (comp (ref "R24")
      (value "0805")
      (footprint "R_0805")
      (description "SMD Chip Resistor - 0805")
      (fields (field (name "TOLERANCE") "?") (field (name "ALTIUM_VALUE") "Value"))
      (libsource (lib "My_Integrated_Lib") (part "RES_0805"))
    )
    (comp (ref "R25")
      (value "0805")
      (footprint "R_0805")
      (description "SMD Chip Resistor - 0805")
      (fields (field (name "TOLERANCE") "?") (field (name "ALTIUM_VALUE") "Value"))
      (libsource (lib "My_Integrated_Lib") (part "RES_0805"))
    )
    (comp (ref "R26")
      (value "0805")
      (footprint "R_0805")
      (description "SMD Chip Resistor - 0805")
      (fields (field (name "TOLERANCE") "?") (field (name "ALTIUM_VALUE") "Value"))
      (libsource (lib "My_Integrated_Lib") (part "RES_0805"))
    )
    (comp (ref "R27")
      (value "0805")
      (footprint "R_0805")
      (description "SMD Chip Resistor - 0805")
      (fields (field (name "TOLERANCE") "?") (field (name "ALTIUM_VALUE") "Value"))
      (libsource (lib "My_Integrated_Lib") (part "RES_0805"))
    )
    (comp (ref "R28")
      (value "0805")
      (footprint "R_0805")
      (description "SMD Chip Resistor - 0805")
      (fields (field (name "TOLERANCE") "?") (field (name "ALTIUM_VALUE") "0R"))
      (libsource (lib "My_Integrated_Lib") (part "RES_0805"))
    )
    (comp (ref "R29")
      (value "0805")
      (footprint "R_0805")
      (description "SMD Chip Resistor - 0805")
      (fields (field (name "TOLERANCE") "?") (field (name "ALTIUM_VALUE") "Value"))
      (libsource (lib "My_Integrated_Lib") (part "RES_0805"))
    )
    (comp (ref "R30")
      (value "0805")
      (footprint "R_0805")
      (description "SMD Chip Resistor - 0805")
      (fields (field (name "TOLERANCE") "?") (field (name "ALTIUM_VALUE") "Value"))
      (libsource (lib "My_Integrated_Lib") (part "RES_0805"))
    )
    (comp (ref "R31")
      (value "0805")
      (footprint "R_0805")
      (description "SMD Chip Resistor - 0805")
      (fields (field (name "TOLERANCE") "?") (field (name "ALTIUM_VALUE") "Value"))
      (libsource (lib "My_Integrated_Lib") (part "RES_0805"))
    )
    (comp (ref "R32")
      (value "0805")
      (footprint "R_0805")
      (description "SMD Chip Resistor - 0805")
      (fields (field (name "TOLERANCE") "?") (field (name "ALTIUM_VALUE") "Value"))
      (libsource (lib "My_Integrated_Lib") (part "RES_0805"))
    )
    (comp (ref "R33")
      (value "0805")
      (footprint "R_0805")
      (description "SMD Chip Resistor - 0805")
      (fields (field (name "TOLERANCE") "?") (field (name "ALTIUM_VALUE") "Value"))
      (libsource (lib "My_Integrated_Lib") (part "RES_0805"))
    )
    (comp (ref "R34")
      (value "0805")
      (footprint "R_0805")
      (description "SMD Chip Resistor - 0805")
      (fields (field (name "TOLERANCE") "?") (field (name "ALTIUM_VALUE") "0R"))
      (libsource (lib "My_Integrated_Lib") (part "RES_0805"))
    )
    (comp (ref "R35")
      (value "0805")
      (footprint "R_0805")
      (description "SMD Chip Resistor - 0805")
      (fields (field (name "TOLERANCE") "?") (field (name "ALTIUM_VALUE") "0R"))
      (libsource (lib "My_Integrated_Lib") (part "RES_0805"))
    )
    (comp (ref "R36")
      (value "WSLP3921L1000FEA")
      (footprint "R_3921")
      (description "Shunt Resistor, 100uR, 9W")
      (fields (field (name "TOLERANCE") "%1") (field (name "ALTIUM_VALUE") "100u") (field (name "WATT") "9W"))
      (libsource (lib "My_Integrated_Lib") (part "RES_SHUNT_100uR_9W"))
    )
    (comp (ref "R37")
      (value "0805")
      (footprint "R_0805")
      (description "SMD Chip Resistor - 0805")
      (fields (field (name "TOLERANCE") "?") (field (name "ALTIUM_VALUE") "Value"))
      (libsource (lib "My_Integrated_Lib") (part "RES_0805"))
    )
    (comp (ref "R38")
      (value "0805")
      (footprint "R_0805")
      (description "SMD Chip Resistor - 0805")
      (fields (field (name "TOLERANCE") "?") (field (name "ALTIUM_VALUE") "Value"))
      (libsource (lib "My_Integrated_Lib") (part "RES_0805"))
    )
    (comp (ref "R39")
      (value "0805")
      (footprint "R_0805")
      (description "SMD Chip Resistor - 0805")
      (fields (field (name "TOLERANCE") "?") (field (name "ALTIUM_VALUE") "Value"))
      (libsource (lib "My_Integrated_Lib") (part "RES_0805"))
    )
    (comp (ref "R40")
      (value "0805")
      (footprint "R_0805")
      (description "SMD Chip Resistor - 0805")
      (fields (field (name "TOLERANCE") "?") (field (name "ALTIUM_VALUE") "Value"))
      (libsource (lib "My_Integrated_Lib") (part "RES_0805"))
    )
    (comp (ref "R41")
      (value "0805")
      (footprint "R_0805")
      (description "SMD Chip Resistor - 0805")
      (fields (field (name "TOLERANCE") "?") (field (name "ALTIUM_VALUE") "Value"))
      (libsource (lib "My_Integrated_Lib") (part "RES_0805"))
    )
    (comp (ref "R42")
      (value "0805")
      (footprint "R_0805")
      (description "SMD Chip Resistor - 0805")
      (fields (field (name "TOLERANCE") "?") (field (name "ALTIUM_VALUE") "0R"))
      (libsource (lib "My_Integrated_Lib") (part "RES_0805"))
    )
    (comp (ref "RT1")
      (value "ERT-J1VG103JA")
      (footprint "R_0603")
      (description "NTC Thermistors 0603 Package")
      (fields
        (field (name "TOLERANCE") "%5")
        (field (name "WATT") "0.1W")
        (field (name "ALTIUM_VALUE") "10K")
      )
      (libsource (lib "My_Integrated_Lib") (part "NTC_0603"))
    )
    (comp (ref "RT2")
      (value "ERT-J1VG103JA")
      (footprint "R_0603")
      (description "NTC Thermistors 0603 Package")
      (fields
        (field (name "TOLERANCE") "%5")
        (field (name "WATT") "0.1W")
        (field (name "ALTIUM_VALUE") "10K")
      )
      (libsource (lib "My_Integrated_Lib") (part "NTC_0603"))
    )
    (comp (ref "RT3")
      (value "ERT-J1VG103JA")
      (footprint "R_0603")
      (description "NTC Thermistors 0603 Package")
      (fields
        (field (name "TOLERANCE") "%5")
        (field (name "WATT") "0.1W")
        (field (name "ALTIUM_VALUE") "10K")
      )
      (libsource (lib "My_Integrated_Lib") (part "NTC_0603"))
    )
    (comp (ref "U1")
      (value "INA181A3IDBVR")
      (footprint "SOT23-6")
      (description "Current Sense Amplifiers, Vos: 100uV, Gain: 100V/V")
      (libsource (lib "My_Integrated_Lib") (part "IC_INA181A3IDBVR"))
    )
    (comp (ref "U2")
      (value "INA181A3IDBVR")
      (footprint "SOT23-6")
      (description "Current Sense Amplifiers, Vos: 100uV, Gain: 100V/V")
      (libsource (lib "My_Integrated_Lib") (part "IC_INA181A3IDBVR"))
    )
    (comp (ref "U3")
      (value "INA181A3IDBVR")
      (footprint "SOT23-6")
      (description "Current Sense Amplifiers, Vos: 100uV, Gain: 100V/V")
      (libsource (lib "My_Integrated_Lib") (part "IC_INA181A3IDBVR"))
    )
  )
  (nets
    (net (code "1") (name "+3V3") (class "Default")
      (node (ref "C1") (pin "1") (pinfunction "1_1") (pintype "passive"))
      (node (ref "C15") (pin "1") (pinfunction "1_1") (pintype "passive"))
      (node (ref "C16") (pin "1") (pinfunction "1_1") (pintype "passive"))
      (node (ref "C2") (pin "1") (pinfunction "1_1") (pintype "passive"))
      (node (ref "C8") (pin "1") (pinfunction "1_1") (pintype "passive"))
      (node (ref "C9") (pin "1") (pinfunction "1_1") (pintype "passive"))
      (node (ref "J1") (pin "1") (pinfunction "1_1") (pintype "passive"))
      (node (ref "J5") (pin "1") (pinfunction "1_1") (pintype "passive"))
      (node (ref "J9") (pin "1") (pinfunction "1_1") (pintype "passive"))
      (node (ref "U1") (pin "6") (pinfunction "VS_6") (pintype "power_in"))
      (node (ref "U2") (pin "6") (pinfunction "VS_6") (pintype "power_in"))
      (node (ref "U3") (pin "6") (pinfunction "VS_6") (pintype "power_in"))
    )
    (net (code "2") (name "/GHA") (class "Default")
      (node (ref "J25") (pin "1") (pinfunction "1_1") (pintype "passive"))
      (node (ref "Q1") (pin "4") (pinfunction "G_4") (pintype "passive"))
      (node (ref "Q2") (pin "4") (pinfunction "G_4") (pintype "passive"))
      (node (ref "Q3") (pin "4") (pinfunction "G_4") (pintype "passive"))
      (node (ref "Q4") (pin "4") (pinfunction "G_4") (pintype "passive"))
      (node (ref "Q5") (pin "4") (pinfunction "G_4") (pintype "passive"))
    )
    (net (code "3") (name "/GHB") (class "Default")
      (node (ref "J26") (pin "1") (pinfunction "1_1") (pintype "passive"))
      (node (ref "Q11") (pin "4") (pinfunction "G_4") (pintype "passive"))
      (node (ref "Q12") (pin "4") (pinfunction "G_4") (pintype "passive"))
      (node (ref "Q13") (pin "4") (pinfunction "G_4") (pintype "passive"))
      (node (ref "Q14") (pin "4") (pinfunction "G_4") (pintype "passive"))
      (node (ref "Q15") (pin "4") (pinfunction "G_4") (pintype "passive"))
    )
    (net (code "4") (name "/GHC") (class "Default")
      (node (ref "J27") (pin "1") (pinfunction "1_1") (pintype "passive"))
      (node (ref "Q21") (pin "4") (pinfunction "G_4") (pintype "passive"))
      (node (ref "Q22") (pin "4") (pinfunction "G_4") (pintype "passive"))
      (node (ref "Q23") (pin "4") (pinfunction "G_4") (pintype "passive"))
      (node (ref "Q24") (pin "4") (pinfunction "G_4") (pintype "passive"))
      (node (ref "Q25") (pin "4") (pinfunction "G_4") (pintype "passive"))
    )
    (net (code "5") (name "/GLA") (class "Default")
      (node (ref "J25") (pin "3") (pinfunction "3_3") (pintype "passive"))
      (node (ref "Q10") (pin "4") (pinfunction "G_4") (pintype "passive"))
      (node (ref "Q6") (pin "4") (pinfunction "G_4") (pintype "passive"))
      (node (ref "Q7") (pin "4") (pinfunction "G_4") (pintype "passive"))
      (node (ref "Q8") (pin "4") (pinfunction "G_4") (pintype "passive"))
      (node (ref "Q9") (pin "4") (pinfunction "G_4") (pintype "passive"))
    )
    (net (code "6") (name "/GLB") (class "Default")
      (node (ref "J26") (pin "3") (pinfunction "3_3") (pintype "passive"))
      (node (ref "Q16") (pin "4") (pinfunction "G_4") (pintype "passive"))
      (node (ref "Q17") (pin "4") (pinfunction "G_4") (pintype "passive"))
      (node (ref "Q18") (pin "4") (pinfunction "G_4") (pintype "passive"))
      (node (ref "Q19") (pin "4") (pinfunction "G_4") (pintype "passive"))
      (node (ref "Q20") (pin "4") (pinfunction "G_4") (pintype "passive"))
    )
    (net (code "7") (name "/GLC") (class "Default")
      (node (ref "J27") (pin "3") (pinfunction "3_3") (pintype "passive"))
      (node (ref "Q26") (pin "4") (pinfunction "G_4") (pintype "passive"))
      (node (ref "Q27") (pin "4") (pinfunction "G_4") (pintype "passive"))
      (node (ref "Q28") (pin "4") (pinfunction "G_4") (pintype "passive"))
      (node (ref "Q29") (pin "4") (pinfunction "G_4") (pintype "passive"))
      (node (ref "Q30") (pin "4") (pinfunction "G_4") (pintype "passive"))
    )
    (net (code "8") (name "/I_PHASE_A") (class "Default")
      (node (ref "J1") (pin "2") (pinfunction "2_2") (pintype "passive"))
      (node (ref "J1") (pin "4") (pinfunction "4_4") (pintype "passive"))
      (node (ref "J1") (pin "6") (pinfunction "6_6") (pintype "passive"))
      (node (ref "U1") (pin "1") (pinfunction "OUT_1") (pintype "passive"))
    )
    (net (code "9") (name "/I_PHASE_B") (class "Default")
      (node (ref "J5") (pin "2") (pinfunction "2_2") (pintype "passive"))
      (node (ref "J5") (pin "4") (pinfunction "4_4") (pintype "passive"))
      (node (ref "J5") (pin "6") (pinfunction "6_6") (pintype "passive"))
      (node (ref "U2") (pin "1") (pinfunction "OUT_1") (pintype "passive"))
    )
    (net (code "10") (name "/I_PHASE_C") (class "Default")
      (node (ref "J9") (pin "2") (pinfunction "2_2") (pintype "passive"))
      (node (ref "J9") (pin "4") (pinfunction "4_4") (pintype "passive"))
      (node (ref "J9") (pin "6") (pinfunction "6_6") (pintype "passive"))
      (node (ref "U3") (pin "1") (pinfunction "OUT_1") (pintype "passive"))
    )
    (net (code "11") (name "/NTC1+") (class "Default")
      (node (ref "J16") (pin "1") (pinfunction "1_1") (pintype "passive"))
      (node (ref "RT1") (pin "1") (pinfunction "1_1") (pintype "passive"))
    )
    (net (code "12") (name "/NTC1-") (class "Default")
      (node (ref "J16") (pin "3") (pinfunction "3_3") (pintype "passive"))
      (node (ref "RT1") (pin "2") (pinfunction "2_2") (pintype "passive"))
    )
    (net (code "13") (name "/NTC2+") (class "Default")
      (node (ref "J20") (pin "1") (pinfunction "1_1") (pintype "passive"))
      (node (ref "RT2") (pin "1") (pinfunction "1_1") (pintype "passive"))
    )
    (net (code "14") (name "/NTC2-") (class "Default")
      (node (ref "J20") (pin "3") (pinfunction "3_3") (pintype "passive"))
      (node (ref "RT2") (pin "2") (pinfunction "2_2") (pintype "passive"))
    )
    (net (code "15") (name "/NTC3+") (class "Default")
      (node (ref "J21") (pin "1") (pinfunction "1_1") (pintype "passive"))
      (node (ref "RT3") (pin "1") (pinfunction "1_1") (pintype "passive"))
    )
    (net (code "16") (name "/NTC3-") (class "Default")
      (node (ref "J21") (pin "3") (pinfunction "3_3") (pintype "passive"))
      (node (ref "RT3") (pin "2") (pinfunction "2_2") (pintype "passive"))
    )
    (net (code "17") (name "/PHASE_A") (class "Default")
      (node (ref "C3") (pin "2") (pinfunction "2_2") (pintype "passive"))
      (node (ref "C4") (pin "2") (pinfunction "2_2") (pintype "passive"))
      (node (ref "C5") (pin "2") (pinfunction "2_2") (pintype "passive"))
      (node (ref "C6") (pin "2") (pinfunction "2_2") (pintype "passive"))
      (node (ref "C7") (pin "2") (pinfunction "2_2") (pintype "passive"))
      (node (ref "D10") (pin "2") (pinfunction "A_2") (pintype "passive"))
      (node (ref "D6") (pin "2") (pinfunction "A_2") (pintype "passive"))
      (node (ref "D7") (pin "2") (pinfunction "A_2") (pintype "passive"))
      (node (ref "D8") (pin "2") (pinfunction "A_2") (pintype "passive"))
      (node (ref "D9") (pin "2") (pinfunction "A_2") (pintype "passive"))
      (node (ref "J13") (pin "1") (pinfunction "1_1") (pintype "passive"))
      (node (ref "J14") (pin "1") (pinfunction "1_1") (pintype "passive"))
      (node (ref "Q1") (pin "1") (pinfunction "S_1_1") (pintype "passive"))
      (node (ref "Q1") (pin "2") (pinfunction "S_2_2") (pintype "passive"))
      (node (ref "Q1") (pin "3") (pinfunction "S_3_3") (pintype "passive"))
      (node (ref "Q10") (pin "5") (pinfunction "D_1_5") (pintype "passive"))
      (node (ref "Q10") (pin "6") (pinfunction "D_2_6") (pintype "passive"))
      (node (ref "Q10") (pin "7") (pinfunction "D_3_7") (pintype "passive"))
      (node (ref "Q10") (pin "8") (pinfunction "D_4_8") (pintype "passive"))
      (node (ref "Q10") (pin "9") (pinfunction "D_5_9") (pintype "passive"))
      (node (ref "Q2") (pin "1") (pinfunction "S_1_1") (pintype "passive"))
      (node (ref "Q2") (pin "2") (pinfunction "S_2_2") (pintype "passive"))
      (node (ref "Q2") (pin "3") (pinfunction "S_3_3") (pintype "passive"))
      (node (ref "Q3") (pin "1") (pinfunction "S_1_1") (pintype "passive"))
      (node (ref "Q3") (pin "2") (pinfunction "S_2_2") (pintype "passive"))
      (node (ref "Q3") (pin "3") (pinfunction "S_3_3") (pintype "passive"))
      (node (ref "Q4") (pin "1") (pinfunction "S_1_1") (pintype "passive"))
      (node (ref "Q4") (pin "2") (pinfunction "S_2_2") (pintype "passive"))
      (node (ref "Q4") (pin "3") (pinfunction "S_3_3") (pintype "passive"))
      (node (ref "Q5") (pin "1") (pinfunction "S_1_1") (pintype "passive"))
      (node (ref "Q5") (pin "2") (pinfunction "S_2_2") (pintype "passive"))
      (node (ref "Q5") (pin "3") (pinfunction "S_3_3") (pintype "passive"))
      (node (ref "Q6") (pin "5") (pinfunction "D_1_5") (pintype "passive"))
      (node (ref "Q6") (pin "6") (pinfunction "D_2_6") (pintype "passive"))
      (node (ref "Q6") (pin "7") (pinfunction "D_3_7") (pintype "passive"))
      (node (ref "Q6") (pin "8") (pinfunction "D_4_8") (pintype "passive"))
      (node (ref "Q6") (pin "9") (pinfunction "D_5_9") (pintype "passive"))
      (node (ref "Q7") (pin "5") (pinfunction "D_1_5") (pintype "passive"))
      (node (ref "Q7") (pin "6") (pinfunction "D_2_6") (pintype "passive"))
      (node (ref "Q7") (pin "7") (pinfunction "D_3_7") (pintype "passive"))
      (node (ref "Q7") (pin "8") (pinfunction "D_4_8") (pintype "passive"))
      (node (ref "Q7") (pin "9") (pinfunction "D_5_9") (pintype "passive"))
      (node (ref "Q8") (pin "5") (pinfunction "D_1_5") (pintype "passive"))
      (node (ref "Q8") (pin "6") (pinfunction "D_2_6") (pintype "passive"))
      (node (ref "Q8") (pin "7") (pinfunction "D_3_7") (pintype "passive"))
      (node (ref "Q8") (pin "8") (pinfunction "D_4_8") (pintype "passive"))
      (node (ref "Q8") (pin "9") (pinfunction "D_5_9") (pintype "passive"))
      (node (ref "Q9") (pin "5") (pinfunction "D_1_5") (pintype "passive"))
      (node (ref "Q9") (pin "6") (pinfunction "D_2_6") (pintype "passive"))
      (node (ref "Q9") (pin "7") (pinfunction "D_3_7") (pintype "passive"))
      (node (ref "Q9") (pin "8") (pinfunction "D_4_8") (pintype "passive"))
      (node (ref "Q9") (pin "9") (pinfunction "D_5_9") (pintype "passive"))
      (node (ref "R10") (pin "1") (pinfunction "1_1") (pintype "passive"))
      (node (ref "R11") (pin "1") (pinfunction "1_1") (pintype "passive"))
      (node (ref "R6") (pin "2") (pinfunction "2_2") (pintype "passive"))
      (node (ref "R7") (pin "1") (pinfunction "1_1") (pintype "passive"))
      (node (ref "R8") (pin "1") (pinfunction "1_1") (pintype "passive"))
      (node (ref "R9") (pin "1") (pinfunction "1_1") (pintype "passive"))
    )
    (net (code "18") (name "/PHASE_B") (class "Default")
      (node (ref "C17") (pin "2") (pinfunction "2_2") (pintype "passive"))
      (node (ref "C18") (pin "2") (pinfunction "2_2") (pintype "passive"))
      (node (ref "C19") (pin "2") (pinfunction "2_2") (pintype "passive"))
      (node (ref "C20") (pin "2") (pinfunction "2_2") (pintype "passive"))
      (node (ref "C21") (pin "2") (pinfunction "2_2") (pintype "passive"))
      (node (ref "D16") (pin "2") (pinfunction "A_2") (pintype "passive"))
      (node (ref "D17") (pin "2") (pinfunction "A_2") (pintype "passive"))
      (node (ref "D18") (pin "2") (pinfunction "A_2") (pintype "passive"))
      (node (ref "D19") (pin "2") (pinfunction "A_2") (pintype "passive"))
      (node (ref "D20") (pin "2") (pinfunction "A_2") (pintype "passive"))
      (node (ref "J15") (pin "1") (pinfunction "1_1") (pintype "passive"))
      (node (ref "J28") (pin "1") (pinfunction "1_1") (pintype "passive"))
      (node (ref "Q11") (pin "1") (pinfunction "S_1_1") (pintype "passive"))
      (node (ref "Q11") (pin "2") (pinfunction "S_2_2") (pintype "passive"))
      (node (ref "Q11") (pin "3") (pinfunction "S_3_3") (pintype "passive"))
      (node (ref "Q12") (pin "1") (pinfunction "S_1_1") (pintype "passive"))
      (node (ref "Q12") (pin "2") (pinfunction "S_2_2") (pintype "passive"))
      (node (ref "Q12") (pin "3") (pinfunction "S_3_3") (pintype "passive"))
      (node (ref "Q13") (pin "1") (pinfunction "S_1_1") (pintype "passive"))
      (node (ref "Q13") (pin "2") (pinfunction "S_2_2") (pintype "passive"))
      (node (ref "Q13") (pin "3") (pinfunction "S_3_3") (pintype "passive"))
      (node (ref "Q14") (pin "1") (pinfunction "S_1_1") (pintype "passive"))
      (node (ref "Q14") (pin "2") (pinfunction "S_2_2") (pintype "passive"))
      (node (ref "Q14") (pin "3") (pinfunction "S_3_3") (pintype "passive"))
      (node (ref "Q15") (pin "1") (pinfunction "S_1_1") (pintype "passive"))
      (node (ref "Q15") (pin "2") (pinfunction "S_2_2") (pintype "passive"))
      (node (ref "Q15") (pin "3") (pinfunction "S_3_3") (pintype "passive"))
      (node (ref "Q16") (pin "5") (pinfunction "D_1_5") (pintype "passive"))
      (node (ref "Q16") (pin "6") (pinfunction "D_2_6") (pintype "passive"))
      (node (ref "Q16") (pin "7") (pinfunction "D_3_7") (pintype "passive"))
      (node (ref "Q16") (pin "8") (pinfunction "D_4_8") (pintype "passive"))
      (node (ref "Q16") (pin "9") (pinfunction "D_5_9") (pintype "passive"))
      (node (ref "Q17") (pin "5") (pinfunction "D_1_5") (pintype "passive"))
      (node (ref "Q17") (pin "6") (pinfunction "D_2_6") (pintype "passive"))
      (node (ref "Q17") (pin "7") (pinfunction "D_3_7") (pintype "passive"))
      (node (ref "Q17") (pin "8") (pinfunction "D_4_8") (pintype "passive"))
      (node (ref "Q17") (pin "9") (pinfunction "D_5_9") (pintype "passive"))
      (node (ref "Q18") (pin "5") (pinfunction "D_1_5") (pintype "passive"))
      (node (ref "Q18") (pin "6") (pinfunction "D_2_6") (pintype "passive"))
      (node (ref "Q18") (pin "7") (pinfunction "D_3_7") (pintype "passive"))
      (node (ref "Q18") (pin "8") (pinfunction "D_4_8") (pintype "passive"))
      (node (ref "Q18") (pin "9") (pinfunction "D_5_9") (pintype "passive"))
      (node (ref "Q19") (pin "5") (pinfunction "D_1_5") (pintype "passive"))
      (node (ref "Q19") (pin "6") (pinfunction "D_2_6") (pintype "passive"))
      (node (ref "Q19") (pin "7") (pinfunction "D_3_7") (pintype "passive"))
      (node (ref "Q19") (pin "8") (pinfunction "D_4_8") (pintype "passive"))
      (node (ref "Q19") (pin "9") (pinfunction "D_5_9") (pintype "passive"))
      (node (ref "Q20") (pin "5") (pinfunction "D_1_5") (pintype "passive"))
      (node (ref "Q20") (pin "6") (pinfunction "D_2_6") (pintype "passive"))
      (node (ref "Q20") (pin "7") (pinfunction "D_3_7") (pintype "passive"))
      (node (ref "Q20") (pin "8") (pinfunction "D_4_8") (pintype "passive"))
      (node (ref "Q20") (pin "9") (pinfunction "D_5_9") (pintype "passive"))
      (node (ref "R20") (pin "2") (pinfunction "2_2") (pintype "passive"))
      (node (ref "R23") (pin "1") (pinfunction "1_1") (pintype "passive"))
      (node (ref "R24") (pin "1") (pinfunction "1_1") (pintype "passive"))
      (node (ref "R25") (pin "1") (pinfunction "1_1") (pintype "passive"))
      (node (ref "R26") (pin "1") (pinfunction "1_1") (pintype "passive"))
      (node (ref "R27") (pin "1") (pinfunction "1_1") (pintype "passive"))
    )
    (net (code "19") (name "/PHASE_C") (class "Default")
      (node (ref "C27") (pin "2") (pinfunction "2_2") (pintype "passive"))
      (node (ref "C28") (pin "2") (pinfunction "2_2") (pintype "passive"))
      (node (ref "C29") (pin "2") (pinfunction "2_2") (pintype "passive"))
      (node (ref "C30") (pin "2") (pinfunction "2_2") (pintype "passive"))
      (node (ref "C31") (pin "2") (pinfunction "2_2") (pintype "passive"))
      (node (ref "D26") (pin "2") (pinfunction "A_2") (pintype "passive"))
      (node (ref "D27") (pin "2") (pinfunction "A_2") (pintype "passive"))
      (node (ref "D28") (pin "2") (pinfunction "A_2") (pintype "passive"))
      (node (ref "D29") (pin "2") (pinfunction "A_2") (pintype "passive"))
      (node (ref "D30") (pin "2") (pinfunction "A_2") (pintype "passive"))
      (node (ref "J29") (pin "1") (pinfunction "1_1") (pintype "passive"))
      (node (ref "J30") (pin "1") (pinfunction "1_1") (pintype "passive"))
      (node (ref "Q21") (pin "1") (pinfunction "S_1_1") (pintype "passive"))
      (node (ref "Q21") (pin "2") (pinfunction "S_2_2") (pintype "passive"))
      (node (ref "Q21") (pin "3") (pinfunction "S_3_3") (pintype "passive"))
      (node (ref "Q22") (pin "1") (pinfunction "S_1_1") (pintype "passive"))
      (node (ref "Q22") (pin "2") (pinfunction "S_2_2") (pintype "passive"))
      (node (ref "Q22") (pin "3") (pinfunction "S_3_3") (pintype "passive"))
      (node (ref "Q23") (pin "1") (pinfunction "S_1_1") (pintype "passive"))
      (node (ref "Q23") (pin "2") (pinfunction "S_2_2") (pintype "passive"))
      (node (ref "Q23") (pin "3") (pinfunction "S_3_3") (pintype "passive"))
      (node (ref "Q24") (pin "1") (pinfunction "S_1_1") (pintype "passive"))
      (node (ref "Q24") (pin "2") (pinfunction "S_2_2") (pintype "passive"))
      (node (ref "Q24") (pin "3") (pinfunction "S_3_3") (pintype "passive"))
      (node (ref "Q25") (pin "1") (pinfunction "S_1_1") (pintype "passive"))
      (node (ref "Q25") (pin "2") (pinfunction "S_2_2") (pintype "passive"))
      (node (ref "Q25") (pin "3") (pinfunction "S_3_3") (pintype "passive"))
      (node (ref "Q26") (pin "5") (pinfunction "D_1_5") (pintype "passive"))
      (node (ref "Q26") (pin "6") (pinfunction "D_2_6") (pintype "passive"))
      (node (ref "Q26") (pin "7") (pinfunction "D_3_7") (pintype "passive"))
      (node (ref "Q26") (pin "8") (pinfunction "D_4_8") (pintype "passive"))
      (node (ref "Q26") (pin "9") (pinfunction "D_5_9") (pintype "passive"))
      (node (ref "Q27") (pin "5") (pinfunction "D_1_5") (pintype "passive"))
      (node (ref "Q27") (pin "6") (pinfunction "D_2_6") (pintype "passive"))
      (node (ref "Q27") (pin "7") (pinfunction "D_3_7") (pintype "passive"))
      (node (ref "Q27") (pin "8") (pinfunction "D_4_8") (pintype "passive"))
      (node (ref "Q27") (pin "9") (pinfunction "D_5_9") (pintype "passive"))
      (node (ref "Q28") (pin "5") (pinfunction "D_1_5") (pintype "passive"))
      (node (ref "Q28") (pin "6") (pinfunction "D_2_6") (pintype "passive"))
      (node (ref "Q28") (pin "7") (pinfunction "D_3_7") (pintype "passive"))
      (node (ref "Q28") (pin "8") (pinfunction "D_4_8") (pintype "passive"))
      (node (ref "Q28") (pin "9") (pinfunction "D_5_9") (pintype "passive"))
      (node (ref "Q29") (pin "5") (pinfunction "D_1_5") (pintype "passive"))
      (node (ref "Q29") (pin "6") (pinfunction "D_2_6") (pintype "passive"))
      (node (ref "Q29") (pin "7") (pinfunction "D_3_7") (pintype "passive"))
      (node (ref "Q29") (pin "8") (pinfunction "D_4_8") (pintype "passive"))
      (node (ref "Q29") (pin "9") (pinfunction "D_5_9") (pintype "passive"))
      (node (ref "Q30") (pin "5") (pinfunction "D_1_5") (pintype "passive"))
      (node (ref "Q30") (pin "6") (pinfunction "D_2_6") (pintype "passive"))
      (node (ref "Q30") (pin "7") (pinfunction "D_3_7") (pintype "passive"))
      (node (ref "Q30") (pin "8") (pinfunction "D_4_8") (pintype "passive"))
      (node (ref "Q30") (pin "9") (pinfunction "D_5_9") (pintype "passive"))
      (node (ref "R34") (pin "2") (pinfunction "2_2") (pintype "passive"))
      (node (ref "R37") (pin "1") (pinfunction "1_1") (pintype "passive"))
      (node (ref "R38") (pin "1") (pinfunction "1_1") (pintype "passive"))
      (node (ref "R39") (pin "1") (pinfunction "1_1") (pintype "passive"))
      (node (ref "R40") (pin "1") (pinfunction "1_1") (pintype "passive"))
      (node (ref "R41") (pin "1") (pinfunction "1_1") (pintype "passive"))
    )
    (net (code "20") (name "/SHUNT_A_N") (class "Default")
      (node (ref "R14") (pin "1") (pinfunction "1_1") (pintype "passive"))
      (node (ref "U1") (pin "4") (pinfunction "IN-_4") (pintype "passive"))
    )
    (net (code "21") (name "/SHUNT_A_P") (class "Default")
      (node (ref "R12") (pin "1") (pinfunction "1_1") (pintype "passive"))
      (node (ref "U1") (pin "3") (pinfunction "IN+_3") (pintype "passive"))
    )
    (net (code "22") (name "/SHUNT_B_N") (class "Default")
      (node (ref "R28") (pin "1") (pinfunction "1_1") (pintype "passive"))
      (node (ref "U2") (pin "4") (pinfunction "IN-_4") (pintype "passive"))
    )
    (net (code "23") (name "/SHUNT_B_P") (class "Default")
      (node (ref "R21") (pin "1") (pinfunction "1_1") (pintype "passive"))
      (node (ref "U2") (pin "3") (pinfunction "IN+_3") (pintype "passive"))
    )
    (net (code "24") (name "/SHUNT_C_N") (class "Default")
      (node (ref "R42") (pin "1") (pinfunction "1_1") (pintype "passive"))
      (node (ref "U3") (pin "4") (pinfunction "IN-_4") (pintype "passive"))
    )
    (net (code "25") (name "/SHUNT_C_P") (class "Default")
      (node (ref "R35") (pin "1") (pinfunction "1_1") (pintype "passive"))
      (node (ref "U3") (pin "3") (pinfunction "IN+_3") (pintype "passive"))
    )
    (net (code "26") (name "/VS_A") (class "Default")
      (node (ref "J22") (pin "1") (pinfunction "1_1") (pintype "passive"))
      (node (ref "J22") (pin "3") (pinfunction "3_3") (pintype "passive"))
      (node (ref "J22") (pin "5") (pinfunction "5_5") (pintype "passive"))
      (node (ref "R6") (pin "1") (pinfunction "1_1") (pintype "passive"))
    )
    (net (code "27") (name "/VS_B") (class "Default")
      (node (ref "J23") (pin "1") (pinfunction "1_1") (pintype "passive"))
      (node (ref "J23") (pin "3") (pinfunction "3_3") (pintype "passive"))
      (node (ref "J23") (pin "5") (pinfunction "5_5") (pintype "passive"))
      (node (ref "R20") (pin "1") (pinfunction "1_1") (pintype "passive"))
    )
    (net (code "28") (name "/VS_C") (class "Default")
      (node (ref "J24") (pin "1") (pinfunction "1_1") (pintype "passive"))
      (node (ref "J24") (pin "3") (pinfunction "3_3") (pintype "passive"))
      (node (ref "J24") (pin "5") (pinfunction "5_5") (pintype "passive"))
      (node (ref "R34") (pin "1") (pinfunction "1_1") (pintype "passive"))
    )
    (net (code "29") (name "GND") (class "Default")
      (node (ref "C1") (pin "2") (pinfunction "2_2") (pintype "passive"))
      (node (ref "C15") (pin "2") (pinfunction "2_2") (pintype "passive"))
      (node (ref "C16") (pin "2") (pinfunction "2_2") (pintype "passive"))
      (node (ref "C2") (pin "2") (pinfunction "2_2") (pintype "passive"))
      (node (ref "C8") (pin "2") (pinfunction "2_2") (pintype "passive"))
      (node (ref "C9") (pin "2") (pinfunction "2_2") (pintype "passive"))
      (node (ref "J1") (pin "3") (pinfunction "3_3") (pintype "passive"))
      (node (ref "J1") (pin "5") (pinfunction "5_5") (pintype "passive"))
      (node (ref "J10") (pin "1") (pinfunction "1_1") (pintype "passive"))
      (node (ref "J11") (pin "1") (pinfunction "1_1") (pintype "passive"))
      (node (ref "J12") (pin "1") (pinfunction "1_1") (pintype "passive"))
      (node (ref "J16") (pin "2") (pinfunction "2_2") (pintype "passive"))
      (node (ref "J16") (pin "4") (pinfunction "4_4") (pintype "passive"))
      (node (ref "J16") (pin "5") (pinfunction "5_5") (pintype "passive"))
      (node (ref "J16") (pin "6") (pinfunction "6_6") (pintype "passive"))
      (node (ref "J17") (pin "1") (pinfunction "1_1") (pintype "passive"))
      (node (ref "J18") (pin "1") (pinfunction "1_1") (pintype "passive"))
      (node (ref "J19") (pin "1") (pinfunction "1_1") (pintype "passive"))
      (node (ref "J20") (pin "2") (pinfunction "2_2") (pintype "passive"))
      (node (ref "J20") (pin "4") (pinfunction "4_4") (pintype "passive"))
      (node (ref "J20") (pin "5") (pinfunction "5_5") (pintype "passive"))
      (node (ref "J20") (pin "6") (pinfunction "6_6") (pintype "passive"))
      (node (ref "J21") (pin "2") (pinfunction "2_2") (pintype "passive"))
      (node (ref "J21") (pin "4") (pinfunction "4_4") (pintype "passive"))
      (node (ref "J21") (pin "5") (pinfunction "5_5") (pintype "passive"))
      (node (ref "J21") (pin "6") (pinfunction "6_6") (pintype "passive"))
      (node (ref "J22") (pin "2") (pinfunction "2_2") (pintype "passive"))
      (node (ref "J22") (pin "4") (pinfunction "4_4") (pintype "passive"))
      (node (ref "J22") (pin "6") (pinfunction "6_6") (pintype "passive"))
      (node (ref "J23") (pin "2") (pinfunction "2_2") (pintype "passive"))
      (node (ref "J23") (pin "4") (pinfunction "4_4") (pintype "passive"))
      (node (ref "J23") (pin "6") (pinfunction "6_6") (pintype "passive"))
      (node (ref "J24") (pin "2") (pinfunction "2_2") (pintype "passive"))
      (node (ref "J24") (pin "4") (pinfunction "4_4") (pintype "passive"))
      (node (ref "J24") (pin "6") (pinfunction "6_6") (pintype "passive"))
      (node (ref "J25") (pin "2") (pinfunction "2_2") (pintype "passive"))
      (node (ref "J25") (pin "4") (pinfunction "4_4") (pintype "passive"))
      (node (ref "J25") (pin "5") (pinfunction "5_5") (pintype "passive"))
      (node (ref "J25") (pin "6") (pinfunction "6_6") (pintype "passive"))
      (node (ref "J26") (pin "2") (pinfunction "2_2") (pintype "passive"))
      (node (ref "J26") (pin "4") (pinfunction "4_4") (pintype "passive"))
      (node (ref "J26") (pin "5") (pinfunction "5_5") (pintype "passive"))
      (node (ref "J26") (pin "6") (pinfunction "6_6") (pintype "passive"))
      (node (ref "J27") (pin "2") (pinfunction "2_2") (pintype "passive"))
      (node (ref "J27") (pin "4") (pinfunction "4_4") (pintype "passive"))
      (node (ref "J27") (pin "5") (pinfunction "5_5") (pintype "passive"))
      (node (ref "J27") (pin "6") (pinfunction "6_6") (pintype "passive"))
      (node (ref "J5") (pin "3") (pinfunction "3_3") (pintype "passive"))
      (node (ref "J5") (pin "5") (pinfunction "5_5") (pintype "passive"))
      (node (ref "J9") (pin "3") (pinfunction "3_3") (pintype "passive"))
      (node (ref "J9") (pin "5") (pinfunction "5_5") (pintype "passive"))
      (node (ref "MH1") (pin "1") (pintype "passive"))
      (node (ref "MH2") (pin "1") (pintype "passive"))
      (node (ref "MH3") (pin "1") (pintype "passive"))
      (node (ref "MH4") (pin "1") (pintype "passive"))
      (node (ref "R13") (pin "1") (pinfunction "1_1") (pintype "passive"))
      (node (ref "R14") (pin "2") (pinfunction "2_2") (pintype "passive"))
      (node (ref "R22") (pin "1") (pinfunction "1_1") (pintype "passive"))
      (node (ref "R28") (pin "2") (pinfunction "2_2") (pintype "passive"))
      (node (ref "R36") (pin "1") (pinfunction "1_1") (pintype "passive"))
      (node (ref "R42") (pin "2") (pinfunction "2_2") (pintype "passive"))
      (node (ref "U1") (pin "2") (pinfunction "GND_2") (pintype "power_in"))
      (node (ref "U1") (pin "5") (pinfunction "REF_5") (pintype "passive"))
      (node (ref "U2") (pin "2") (pinfunction "GND_2") (pintype "power_in"))
      (node (ref "U2") (pin "5") (pinfunction "REF_5") (pintype "passive"))
      (node (ref "U3") (pin "2") (pinfunction "GND_2") (pintype "power_in"))
      (node (ref "U3") (pin "5") (pinfunction "REF_5") (pintype "passive"))
    )
    (net (code "30") (name "Net-(D1-K)") (class "Default")
      (node (ref "C3") (pin "1") (pinfunction "1_1") (pintype "passive"))
      (node (ref "D1") (pin "1") (pinfunction "K_1") (pintype "passive"))
      (node (ref "R1") (pin "2") (pinfunction "2_2") (pintype "passive"))
    )
    (net (code "31") (name "Net-(D2-K)") (class "Default")
      (node (ref "C4") (pin "1") (pinfunction "1_1") (pintype "passive"))
      (node (ref "D2") (pin "1") (pinfunction "K_1") (pintype "passive"))
      (node (ref "R2") (pin "2") (pinfunction "2_2") (pintype "passive"))
    )
    (net (code "32") (name "Net-(D3-K)") (class "Default")
      (node (ref "C5") (pin "1") (pinfunction "1_1") (pintype "passive"))
      (node (ref "D3") (pin "1") (pinfunction "K_1") (pintype "passive"))
      (node (ref "R3") (pin "2") (pinfunction "2_2") (pintype "passive"))
    )
    (net (code "33") (name "Net-(D4-K)") (class "Default")
      (node (ref "C6") (pin "1") (pinfunction "1_1") (pintype "passive"))
      (node (ref "D4") (pin "1") (pinfunction "K_1") (pintype "passive"))
      (node (ref "R4") (pin "2") (pinfunction "2_2") (pintype "passive"))
    )
    (net (code "34") (name "Net-(D5-K)") (class "Default")
      (node (ref "C7") (pin "1") (pinfunction "1_1") (pintype "passive"))
      (node (ref "D5") (pin "1") (pinfunction "K_1") (pintype "passive"))
      (node (ref "R5") (pin "2") (pinfunction "2_2") (pintype "passive"))
    )
    (net (code "35") (name "Net-(D6-K)") (class "Default")
      (node (ref "C10") (pin "1") (pinfunction "1_1") (pintype "passive"))
      (node (ref "D6") (pin "1") (pinfunction "K_1") (pintype "passive"))
      (node (ref "R7") (pin "2") (pinfunction "2_2") (pintype "passive"))
    )
    (net (code "36") (name "Net-(D7-K)") (class "Default")
      (node (ref "C11") (pin "1") (pinfunction "1_1") (pintype "passive"))
      (node (ref "D7") (pin "1") (pinfunction "K_1") (pintype "passive"))
      (node (ref "R8") (pin "2") (pinfunction "2_2") (pintype "passive"))
    )
    (net (code "37") (name "Net-(D8-K)") (class "Default")
      (node (ref "C12") (pin "1") (pinfunction "1_1") (pintype "passive"))
      (node (ref "D8") (pin "1") (pinfunction "K_1") (pintype "passive"))
      (node (ref "R9") (pin "2") (pinfunction "2_2") (pintype "passive"))
    )
    (net (code "38") (name "Net-(D9-K)") (class "Default")
      (node (ref "C13") (pin "1") (pinfunction "1_1") (pintype "passive"))
      (node (ref "D9") (pin "1") (pinfunction "K_1") (pintype "passive"))
      (node (ref "R10") (pin "2") (pinfunction "2_2") (pintype "passive"))
    )
    (net (code "39") (name "Net-(D10-K)") (class "Default")
      (node (ref "C14") (pin "1") (pinfunction "1_1") (pintype "passive"))
      (node (ref "D10") (pin "1") (pinfunction "K_1") (pintype "passive"))
      (node (ref "R11") (pin "2") (pinfunction "2_2") (pintype "passive"))
    )
    (net (code "40") (name "Net-(D11-K)") (class "Default")
      (node (ref "C17") (pin "1") (pinfunction "1_1") (pintype "passive"))
      (node (ref "D11") (pin "1") (pinfunction "K_1") (pintype "passive"))
      (node (ref "R15") (pin "2") (pinfunction "2_2") (pintype "passive"))
    )
    (net (code "41") (name "Net-(D12-K)") (class "Default")
      (node (ref "C18") (pin "1") (pinfunction "1_1") (pintype "passive"))
      (node (ref "D12") (pin "1") (pinfunction "K_1") (pintype "passive"))
      (node (ref "R16") (pin "2") (pinfunction "2_2") (pintype "passive"))
    )
    (net (code "42") (name "Net-(D13-K)") (class "Default")
      (node (ref "C19") (pin "1") (pinfunction "1_1") (pintype "passive"))
      (node (ref "D13") (pin "1") (pinfunction "K_1") (pintype "passive"))
      (node (ref "R17") (pin "2") (pinfunction "2_2") (pintype "passive"))
    )
    (net (code "43") (name "Net-(D14-K)") (class "Default")
      (node (ref "C20") (pin "1") (pinfunction "1_1") (pintype "passive"))
      (node (ref "D14") (pin "1") (pinfunction "K_1") (pintype "passive"))
      (node (ref "R18") (pin "2") (pinfunction "2_2") (pintype "passive"))
    )
    (net (code "44") (name "Net-(D15-K)") (class "Default")
      (node (ref "C21") (pin "1") (pinfunction "1_1") (pintype "passive"))
      (node (ref "D15") (pin "1") (pinfunction "K_1") (pintype "passive"))
      (node (ref "R19") (pin "2") (pinfunction "2_2") (pintype "passive"))
    )
    (net (code "45") (name "Net-(D16-K)") (class "Default")
      (node (ref "C22") (pin "1") (pinfunction "1_1") (pintype "passive"))
      (node (ref "D16") (pin "1") (pinfunction "K_1") (pintype "passive"))
      (node (ref "R23") (pin "2") (pinfunction "2_2") (pintype "passive"))
    )
    (net (code "46") (name "Net-(D17-K)") (class "Default")
      (node (ref "C23") (pin "1") (pinfunction "1_1") (pintype "passive"))
      (node (ref "D17") (pin "1") (pinfunction "K_1") (pintype "passive"))
      (node (ref "R24") (pin "2") (pinfunction "2_2") (pintype "passive"))
    )
    (net (code "47") (name "Net-(D18-K)") (class "Default")
      (node (ref "C24") (pin "1") (pinfunction "1_1") (pintype "passive"))
      (node (ref "D18") (pin "1") (pinfunction "K_1") (pintype "passive"))
      (node (ref "R25") (pin "2") (pinfunction "2_2") (pintype "passive"))
    )
    (net (code "48") (name "Net-(D19-K)") (class "Default")
      (node (ref "C25") (pin "1") (pinfunction "1_1") (pintype "passive"))
      (node (ref "D19") (pin "1") (pinfunction "K_1") (pintype "passive"))
      (node (ref "R26") (pin "2") (pinfunction "2_2") (pintype "passive"))
    )
    (net (code "49") (name "Net-(D20-K)") (class "Default")
      (node (ref "C26") (pin "1") (pinfunction "1_1") (pintype "passive"))
      (node (ref "D20") (pin "1") (pinfunction "K_1") (pintype "passive"))
      (node (ref "R27") (pin "2") (pinfunction "2_2") (pintype "passive"))
    )
    (net (code "50") (name "Net-(D21-K)") (class "Default")
      (node (ref "C27") (pin "1") (pinfunction "1_1") (pintype "passive"))
      (node (ref "D21") (pin "1") (pinfunction "K_1") (pintype "passive"))
      (node (ref "R29") (pin "2") (pinfunction "2_2") (pintype "passive"))
    )
    (net (code "51") (name "Net-(D22-K)") (class "Default")
      (node (ref "C28") (pin "1") (pinfunction "1_1") (pintype "passive"))
      (node (ref "D22") (pin "1") (pinfunction "K_1") (pintype "passive"))
      (node (ref "R30") (pin "2") (pinfunction "2_2") (pintype "passive"))
    )
    (net (code "52") (name "Net-(D23-K)") (class "Default")
      (node (ref "C29") (pin "1") (pinfunction "1_1") (pintype "passive"))
      (node (ref "D23") (pin "1") (pinfunction "K_1") (pintype "passive"))
      (node (ref "R31") (pin "2") (pinfunction "2_2") (pintype "passive"))
    )
    (net (code "53") (name "Net-(D24-K)") (class "Default")
      (node (ref "C30") (pin "1") (pinfunction "1_1") (pintype "passive"))
      (node (ref "D24") (pin "1") (pinfunction "K_1") (pintype "passive"))
      (node (ref "R32") (pin "2") (pinfunction "2_2") (pintype "passive"))
    )
    (net (code "54") (name "Net-(D25-K)") (class "Default")
      (node (ref "C31") (pin "1") (pinfunction "1_1") (pintype "passive"))
      (node (ref "D25") (pin "1") (pinfunction "K_1") (pintype "passive"))
      (node (ref "R33") (pin "2") (pinfunction "2_2") (pintype "passive"))
    )
    (net (code "55") (name "Net-(D26-K)") (class "Default")
      (node (ref "C32") (pin "1") (pinfunction "1_1") (pintype "passive"))
      (node (ref "D26") (pin "1") (pinfunction "K_1") (pintype "passive"))
      (node (ref "R37") (pin "2") (pinfunction "2_2") (pintype "passive"))
    )
    (net (code "56") (name "Net-(D27-K)") (class "Default")
      (node (ref "C33") (pin "1") (pinfunction "1_1") (pintype "passive"))
      (node (ref "D27") (pin "1") (pinfunction "K_1") (pintype "passive"))
      (node (ref "R38") (pin "2") (pinfunction "2_2") (pintype "passive"))
    )
    (net (code "57") (name "Net-(D28-K)") (class "Default")
      (node (ref "C34") (pin "1") (pinfunction "1_1") (pintype "passive"))
      (node (ref "D28") (pin "1") (pinfunction "K_1") (pintype "passive"))
      (node (ref "R39") (pin "2") (pinfunction "2_2") (pintype "passive"))
    )
    (net (code "58") (name "Net-(D29-K)") (class "Default")
      (node (ref "C35") (pin "1") (pinfunction "1_1") (pintype "passive"))
      (node (ref "D29") (pin "1") (pinfunction "K_1") (pintype "passive"))
      (node (ref "R40") (pin "2") (pinfunction "2_2") (pintype "passive"))
    )
    (net (code "59") (name "Net-(D30-K)") (class "Default")
      (node (ref "C36") (pin "1") (pinfunction "1_1") (pintype "passive"))
      (node (ref "D30") (pin "1") (pinfunction "K_1") (pintype "passive"))
      (node (ref "R41") (pin "2") (pinfunction "2_2") (pintype "passive"))
    )
    (net (code "60") (name "Net-(Q10-S_1)") (class "Default")
      (node (ref "C10") (pin "2") (pinfunction "2_2") (pintype "passive"))
      (node (ref "C11") (pin "2") (pinfunction "2_2") (pintype "passive"))
      (node (ref "C12") (pin "2") (pinfunction "2_2") (pintype "passive"))
      (node (ref "C13") (pin "2") (pinfunction "2_2") (pintype "passive"))
      (node (ref "C14") (pin "2") (pinfunction "2_2") (pintype "passive"))
      (node (ref "Q10") (pin "1") (pinfunction "S_1_1") (pintype "passive"))
      (node (ref "Q10") (pin "2") (pinfunction "S_2_2") (pintype "passive"))
      (node (ref "Q10") (pin "3") (pinfunction "S_3_3") (pintype "passive"))
      (node (ref "Q6") (pin "1") (pinfunction "S_1_1") (pintype "passive"))
      (node (ref "Q6") (pin "2") (pinfunction "S_2_2") (pintype "passive"))
      (node (ref "Q6") (pin "3") (pinfunction "S_3_3") (pintype "passive"))
      (node (ref "Q7") (pin "1") (pinfunction "S_1_1") (pintype "passive"))
      (node (ref "Q7") (pin "2") (pinfunction "S_2_2") (pintype "passive"))
      (node (ref "Q7") (pin "3") (pinfunction "S_3_3") (pintype "passive"))
      (node (ref "Q8") (pin "1") (pinfunction "S_1_1") (pintype "passive"))
      (node (ref "Q8") (pin "2") (pinfunction "S_2_2") (pintype "passive"))
      (node (ref "Q8") (pin "3") (pinfunction "S_3_3") (pintype "passive"))
      (node (ref "Q9") (pin "1") (pinfunction "S_1_1") (pintype "passive"))
      (node (ref "Q9") (pin "2") (pinfunction "S_2_2") (pintype "passive"))
      (node (ref "Q9") (pin "3") (pinfunction "S_3_3") (pintype "passive"))
      (node (ref "R12") (pin "2") (pinfunction "2_2") (pintype "passive"))
      (node (ref "R13") (pin "2") (pinfunction "2_2") (pintype "passive"))
    )
    (net (code "61") (name "Net-(Q16-S_1)") (class "Default")
      (node (ref "C22") (pin "2") (pinfunction "2_2") (pintype "passive"))
      (node (ref "C23") (pin "2") (pinfunction "2_2") (pintype "passive"))
      (node (ref "C24") (pin "2") (pinfunction "2_2") (pintype "passive"))
      (node (ref "C25") (pin "2") (pinfunction "2_2") (pintype "passive"))
      (node (ref "C26") (pin "2") (pinfunction "2_2") (pintype "passive"))
      (node (ref "Q16") (pin "1") (pinfunction "S_1_1") (pintype "passive"))
      (node (ref "Q16") (pin "2") (pinfunction "S_2_2") (pintype "passive"))
      (node (ref "Q16") (pin "3") (pinfunction "S_3_3") (pintype "passive"))
      (node (ref "Q17") (pin "1") (pinfunction "S_1_1") (pintype "passive"))
      (node (ref "Q17") (pin "2") (pinfunction "S_2_2") (pintype "passive"))
      (node (ref "Q17") (pin "3") (pinfunction "S_3_3") (pintype "passive"))
      (node (ref "Q18") (pin "1") (pinfunction "S_1_1") (pintype "passive"))
      (node (ref "Q18") (pin "2") (pinfunction "S_2_2") (pintype "passive"))
      (node (ref "Q18") (pin "3") (pinfunction "S_3_3") (pintype "passive"))
      (node (ref "Q19") (pin "1") (pinfunction "S_1_1") (pintype "passive"))
      (node (ref "Q19") (pin "2") (pinfunction "S_2_2") (pintype "passive"))
      (node (ref "Q19") (pin "3") (pinfunction "S_3_3") (pintype "passive"))
      (node (ref "Q20") (pin "1") (pinfunction "S_1_1") (pintype "passive"))
      (node (ref "Q20") (pin "2") (pinfunction "S_2_2") (pintype "passive"))
      (node (ref "Q20") (pin "3") (pinfunction "S_3_3") (pintype "passive"))
      (node (ref "R21") (pin "2") (pinfunction "2_2") (pintype "passive"))
      (node (ref "R22") (pin "2") (pinfunction "2_2") (pintype "passive"))
    )
    (net (code "62") (name "Net-(Q26-S_1)") (class "Default")
      (node (ref "C32") (pin "2") (pinfunction "2_2") (pintype "passive"))
      (node (ref "C33") (pin "2") (pinfunction "2_2") (pintype "passive"))
      (node (ref "C34") (pin "2") (pinfunction "2_2") (pintype "passive"))
      (node (ref "C35") (pin "2") (pinfunction "2_2") (pintype "passive"))
      (node (ref "C36") (pin "2") (pinfunction "2_2") (pintype "passive"))
      (node (ref "Q26") (pin "1") (pinfunction "S_1_1") (pintype "passive"))
      (node (ref "Q26") (pin "2") (pinfunction "S_2_2") (pintype "passive"))
      (node (ref "Q26") (pin "3") (pinfunction "S_3_3") (pintype "passive"))
      (node (ref "Q27") (pin "1") (pinfunction "S_1_1") (pintype "passive"))
      (node (ref "Q27") (pin "2") (pinfunction "S_2_2") (pintype "passive"))
      (node (ref "Q27") (pin "3") (pinfunction "S_3_3") (pintype "passive"))
      (node (ref "Q28") (pin "1") (pinfunction "S_1_1") (pintype "passive"))
      (node (ref "Q28") (pin "2") (pinfunction "S_2_2") (pintype "passive"))
      (node (ref "Q28") (pin "3") (pinfunction "S_3_3") (pintype "passive"))
      (node (ref "Q29") (pin "1") (pinfunction "S_1_1") (pintype "passive"))
      (node (ref "Q29") (pin "2") (pinfunction "S_2_2") (pintype "passive"))
      (node (ref "Q29") (pin "3") (pinfunction "S_3_3") (pintype "passive"))
      (node (ref "Q30") (pin "1") (pinfunction "S_1_1") (pintype "passive"))
      (node (ref "Q30") (pin "2") (pinfunction "S_2_2") (pintype "passive"))
      (node (ref "Q30") (pin "3") (pinfunction "S_3_3") (pintype "passive"))
      (node (ref "R35") (pin "2") (pinfunction "2_2") (pintype "passive"))
      (node (ref "R36") (pin "2") (pinfunction "2_2") (pintype "passive"))
    )
    (net (code "63") (name "VIN") (class "Default")
      (node (ref "D1") (pin "2") (pinfunction "A_2") (pintype "passive"))
      (node (ref "D11") (pin "2") (pinfunction "A_2") (pintype "passive"))
      (node (ref "D12") (pin "2") (pinfunction "A_2") (pintype "passive"))
      (node (ref "D13") (pin "2") (pinfunction "A_2") (pintype "passive"))
      (node (ref "D14") (pin "2") (pinfunction "A_2") (pintype "passive"))
      (node (ref "D15") (pin "2") (pinfunction "A_2") (pintype "passive"))
      (node (ref "D2") (pin "2") (pinfunction "A_2") (pintype "passive"))
      (node (ref "D21") (pin "2") (pinfunction "A_2") (pintype "passive"))
      (node (ref "D22") (pin "2") (pinfunction "A_2") (pintype "passive"))
      (node (ref "D23") (pin "2") (pinfunction "A_2") (pintype "passive"))
      (node (ref "D24") (pin "2") (pinfunction "A_2") (pintype "passive"))
      (node (ref "D25") (pin "2") (pinfunction "A_2") (pintype "passive"))
      (node (ref "D3") (pin "2") (pinfunction "A_2") (pintype "passive"))
      (node (ref "D4") (pin "2") (pinfunction "A_2") (pintype "passive"))
      (node (ref "D5") (pin "2") (pinfunction "A_2") (pintype "passive"))
      (node (ref "J2") (pin "1") (pinfunction "1_1") (pintype "passive"))
      (node (ref "J3") (pin "1") (pinfunction "1_1") (pintype "passive"))
      (node (ref "J4") (pin "1") (pinfunction "1_1") (pintype "passive"))
      (node (ref "J6") (pin "1") (pinfunction "1_1") (pintype "passive"))
      (node (ref "J7") (pin "1") (pinfunction "1_1") (pintype "passive"))
      (node (ref "J8") (pin "1") (pinfunction "1_1") (pintype "passive"))
      (node (ref "Q1") (pin "5") (pinfunction "D_1_5") (pintype "passive"))
      (node (ref "Q1") (pin "6") (pinfunction "D_2_6") (pintype "passive"))
      (node (ref "Q1") (pin "7") (pinfunction "D_3_7") (pintype "passive"))
      (node (ref "Q1") (pin "8") (pinfunction "D_4_8") (pintype "passive"))
      (node (ref "Q1") (pin "9") (pinfunction "D_5_9") (pintype "passive"))
      (node (ref "Q11") (pin "5") (pinfunction "D_1_5") (pintype "passive"))
      (node (ref "Q11") (pin "6") (pinfunction "D_2_6") (pintype "passive"))
      (node (ref "Q11") (pin "7") (pinfunction "D_3_7") (pintype "passive"))
      (node (ref "Q11") (pin "8") (pinfunction "D_4_8") (pintype "passive"))
      (node (ref "Q11") (pin "9") (pinfunction "D_5_9") (pintype "passive"))
      (node (ref "Q12") (pin "5") (pinfunction "D_1_5") (pintype "passive"))
      (node (ref "Q12") (pin "6") (pinfunction "D_2_6") (pintype "passive"))
      (node (ref "Q12") (pin "7") (pinfunction "D_3_7") (pintype "passive"))
      (node (ref "Q12") (pin "8") (pinfunction "D_4_8") (pintype "passive"))
      (node (ref "Q12") (pin "9") (pinfunction "D_5_9") (pintype "passive"))
      (node (ref "Q13") (pin "5") (pinfunction "D_1_5") (pintype "passive"))
      (node (ref "Q13") (pin "6") (pinfunction "D_2_6") (pintype "passive"))
      (node (ref "Q13") (pin "7") (pinfunction "D_3_7") (pintype "passive"))
      (node (ref "Q13") (pin "8") (pinfunction "D_4_8") (pintype "passive"))
      (node (ref "Q13") (pin "9") (pinfunction "D_5_9") (pintype "passive"))
      (node (ref "Q14") (pin "5") (pinfunction "D_1_5") (pintype "passive"))
      (node (ref "Q14") (pin "6") (pinfunction "D_2_6") (pintype "passive"))
      (node (ref "Q14") (pin "7") (pinfunction "D_3_7") (pintype "passive"))
      (node (ref "Q14") (pin "8") (pinfunction "D_4_8") (pintype "passive"))
      (node (ref "Q14") (pin "9") (pinfunction "D_5_9") (pintype "passive"))
      (node (ref "Q15") (pin "5") (pinfunction "D_1_5") (pintype "passive"))
      (node (ref "Q15") (pin "6") (pinfunction "D_2_6") (pintype "passive"))
      (node (ref "Q15") (pin "7") (pinfunction "D_3_7") (pintype "passive"))
      (node (ref "Q15") (pin "8") (pinfunction "D_4_8") (pintype "passive"))
      (node (ref "Q15") (pin "9") (pinfunction "D_5_9") (pintype "passive"))
      (node (ref "Q2") (pin "5") (pinfunction "D_1_5") (pintype "passive"))
      (node (ref "Q2") (pin "6") (pinfunction "D_2_6") (pintype "passive"))
      (node (ref "Q2") (pin "7") (pinfunction "D_3_7") (pintype "passive"))
      (node (ref "Q2") (pin "8") (pinfunction "D_4_8") (pintype "passive"))
      (node (ref "Q2") (pin "9") (pinfunction "D_5_9") (pintype "passive"))
      (node (ref "Q21") (pin "5") (pinfunction "D_1_5") (pintype "passive"))
      (node (ref "Q21") (pin "6") (pinfunction "D_2_6") (pintype "passive"))
      (node (ref "Q21") (pin "7") (pinfunction "D_3_7") (pintype "passive"))
      (node (ref "Q21") (pin "8") (pinfunction "D_4_8") (pintype "passive"))
      (node (ref "Q21") (pin "9") (pinfunction "D_5_9") (pintype "passive"))
      (node (ref "Q22") (pin "5") (pinfunction "D_1_5") (pintype "passive"))
      (node (ref "Q22") (pin "6") (pinfunction "D_2_6") (pintype "passive"))
      (node (ref "Q22") (pin "7") (pinfunction "D_3_7") (pintype "passive"))
      (node (ref "Q22") (pin "8") (pinfunction "D_4_8") (pintype "passive"))
      (node (ref "Q22") (pin "9") (pinfunction "D_5_9") (pintype "passive"))
      (node (ref "Q23") (pin "5") (pinfunction "D_1_5") (pintype "passive"))
      (node (ref "Q23") (pin "6") (pinfunction "D_2_6") (pintype "passive"))
      (node (ref "Q23") (pin "7") (pinfunction "D_3_7") (pintype "passive"))
      (node (ref "Q23") (pin "8") (pinfunction "D_4_8") (pintype "passive"))
      (node (ref "Q23") (pin "9") (pinfunction "D_5_9") (pintype "passive"))
      (node (ref "Q24") (pin "5") (pinfunction "D_1_5") (pintype "passive"))
      (node (ref "Q24") (pin "6") (pinfunction "D_2_6") (pintype "passive"))
      (node (ref "Q24") (pin "7") (pinfunction "D_3_7") (pintype "passive"))
      (node (ref "Q24") (pin "8") (pinfunction "D_4_8") (pintype "passive"))
      (node (ref "Q24") (pin "9") (pinfunction "D_5_9") (pintype "passive"))
      (node (ref "Q25") (pin "5") (pinfunction "D_1_5") (pintype "passive"))
      (node (ref "Q25") (pin "6") (pinfunction "D_2_6") (pintype "passive"))
      (node (ref "Q25") (pin "7") (pinfunction "D_3_7") (pintype "passive"))
      (node (ref "Q25") (pin "8") (pinfunction "D_4_8") (pintype "passive"))
      (node (ref "Q25") (pin "9") (pinfunction "D_5_9") (pintype "passive"))
      (node (ref "Q3") (pin "5") (pinfunction "D_1_5") (pintype "passive"))
      (node (ref "Q3") (pin "6") (pinfunction "D_2_6") (pintype "passive"))
      (node (ref "Q3") (pin "7") (pinfunction "D_3_7") (pintype "passive"))
      (node (ref "Q3") (pin "8") (pinfunction "D_4_8") (pintype "passive"))
      (node (ref "Q3") (pin "9") (pinfunction "D_5_9") (pintype "passive"))
      (node (ref "Q4") (pin "5") (pinfunction "D_1_5") (pintype "passive"))
      (node (ref "Q4") (pin "6") (pinfunction "D_2_6") (pintype "passive"))
      (node (ref "Q4") (pin "7") (pinfunction "D_3_7") (pintype "passive"))
      (node (ref "Q4") (pin "8") (pinfunction "D_4_8") (pintype "passive"))
      (node (ref "Q4") (pin "9") (pinfunction "D_5_9") (pintype "passive"))
      (node (ref "Q5") (pin "5") (pinfunction "D_1_5") (pintype "passive"))
      (node (ref "Q5") (pin "6") (pinfunction "D_2_6") (pintype "passive"))
      (node (ref "Q5") (pin "7") (pinfunction "D_3_7") (pintype "passive"))
      (node (ref "Q5") (pin "8") (pinfunction "D_4_8") (pintype "passive"))
      (node (ref "Q5") (pin "9") (pinfunction "D_5_9") (pintype "passive"))
      (node (ref "R1") (pin "1") (pinfunction "1_1") (pintype "passive"))
      (node (ref "R15") (pin "1") (pinfunction "1_1") (pintype "passive"))
      (node (ref "R16") (pin "1") (pinfunction "1_1") (pintype "passive"))
      (node (ref "R17") (pin "1") (pinfunction "1_1") (pintype "passive"))
      (node (ref "R18") (pin "1") (pinfunction "1_1") (pintype "passive"))
      (node (ref "R19") (pin "1") (pinfunction "1_1") (pintype "passive"))
      (node (ref "R2") (pin "1") (pinfunction "1_1") (pintype "passive"))
      (node (ref "R29") (pin "1") (pinfunction "1_1") (pintype "passive"))
      (node (ref "R3") (pin "1") (pinfunction "1_1") (pintype "passive"))
      (node (ref "R30") (pin "1") (pinfunction "1_1") (pintype "passive"))
      (node (ref "R31") (pin "1") (pinfunction "1_1") (pintype "passive"))
      (node (ref "R32") (pin "1") (pinfunction "1_1") (pintype "passive"))
      (node (ref "R33") (pin "1") (pinfunction "1_1") (pintype "passive"))
      (node (ref "R4") (pin "1") (pinfunction "1_1") (pintype "passive"))
      (node (ref "R5") (pin "1") (pinfunction "1_1") (pintype "passive"))
    )
  )
)
